# ARM_board.net
KiCad netlist of a schematic drawn in EAGLE
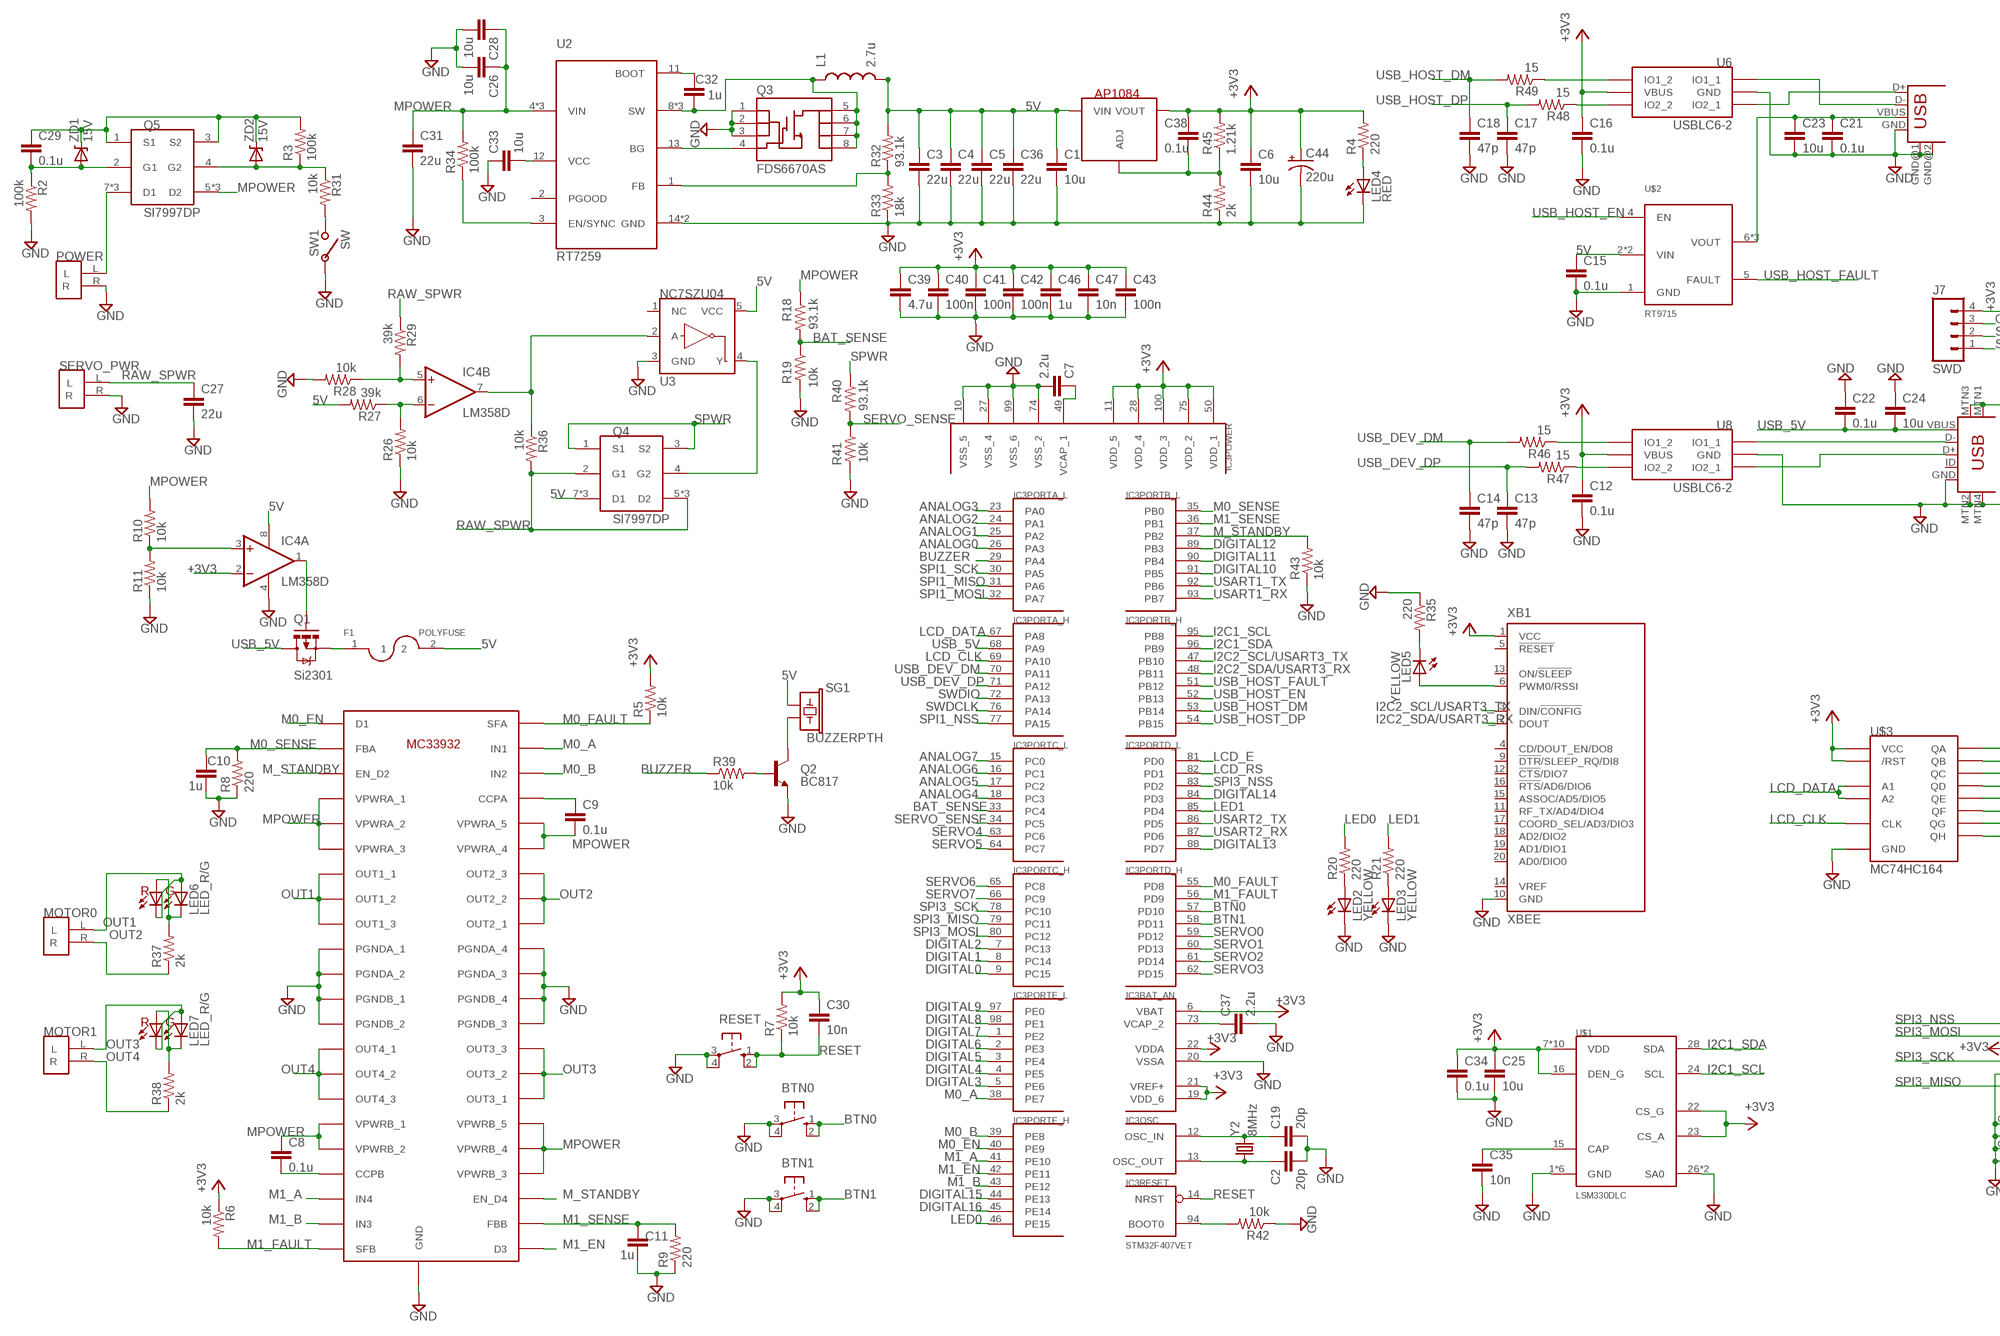
[diagram p0: schematic, sheet 1, part 1 of 2]
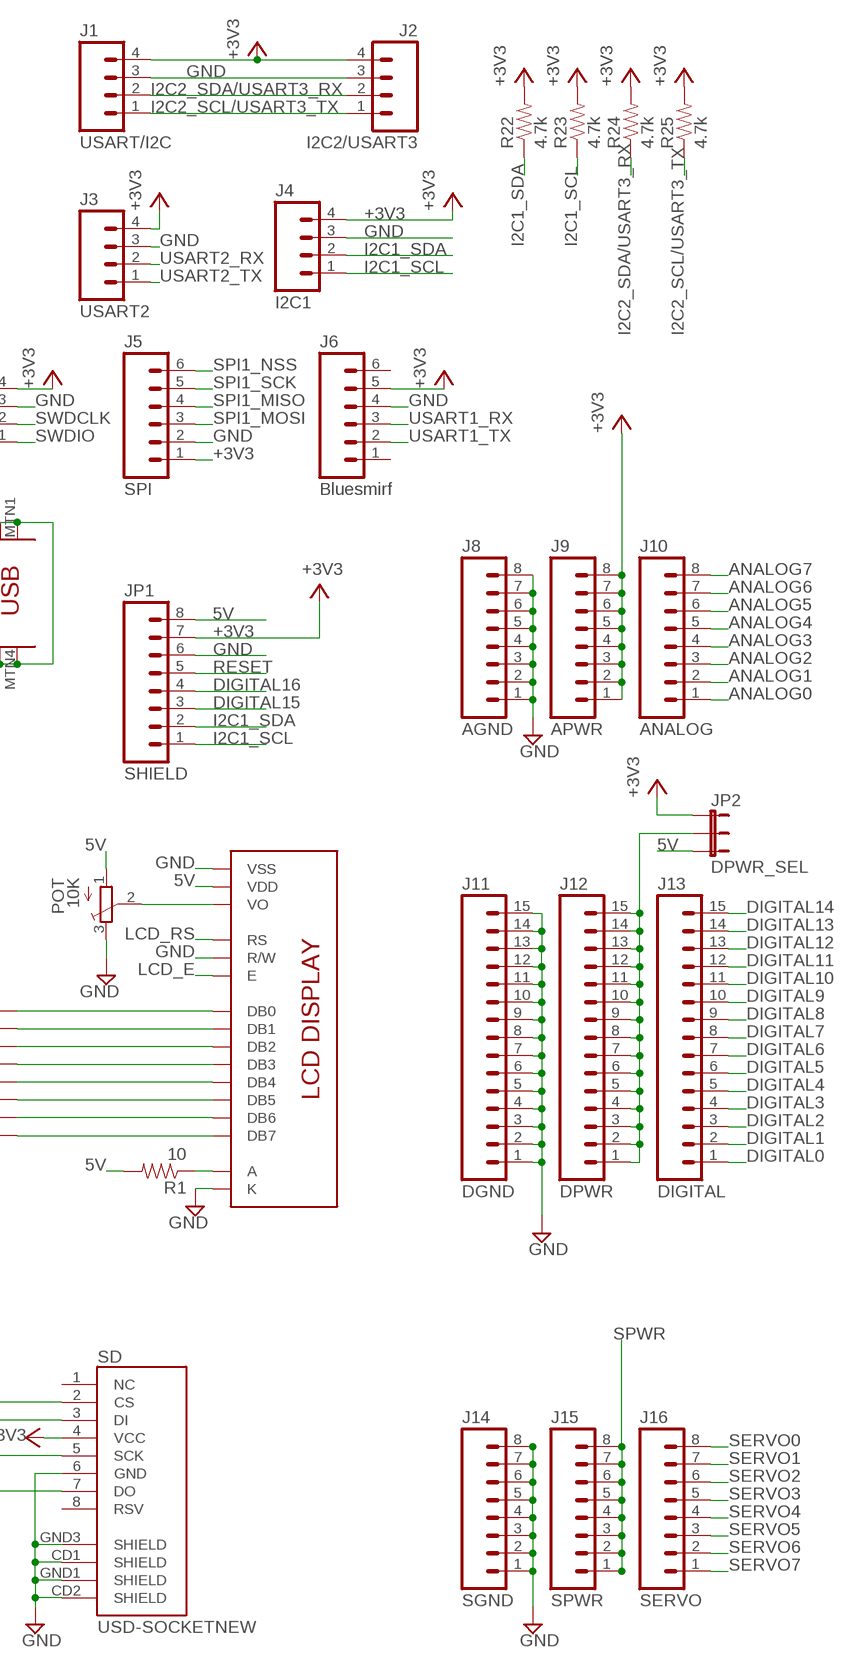
[diagram p1: schematic, sheet 1, part 2 of 2]

(export (version "E")
  (design (tool "Eeschema 10.0.6"))
  (components
    (comp (ref "AP1084")
      (value "AP1084")
      (footprint "eagle-import:DPAK")
      (libsource (lib "eagle-import") (part "AP1084"))
    )
    (comp (ref "BTN0")
      (value "10-XX")
      (footprint "eagle-import:B3F-10XX")
      (fields (field (name "MPN") "B3F-1000"))
      (libsource (lib "eagle-import") (part "10-XX"))
    )
    (comp (ref "BTN1")
      (value "10-XX")
      (footprint "eagle-import:B3F-10XX")
      (fields (field (name "MPN") "B3F-1000"))
      (libsource (lib "eagle-import") (part "10-XX"))
    )
    (comp (ref "C1")
      (value "10u")
      (footprint "eagle-import:0805")
      (libsource (lib "eagle-import") (part "CAP0805"))
    )
    (comp (ref "C2")
      (value "20p")
      (footprint "eagle-import:0603-CAP")
      (libsource (lib "eagle-import") (part "CAP0603-CAP"))
    )
    (comp (ref "C3")
      (value "22u")
      (footprint "eagle-import:0805")
      (libsource (lib "eagle-import") (part "CAP0805"))
    )
    (comp (ref "C4")
      (value "22u")
      (footprint "eagle-import:0805")
      (libsource (lib "eagle-import") (part "CAP0805"))
    )
    (comp (ref "C5")
      (value "22u")
      (footprint "eagle-import:0805")
      (libsource (lib "eagle-import") (part "CAP0805"))
    )
    (comp (ref "C6")
      (value "10u")
      (footprint "eagle-import:0805")
      (libsource (lib "eagle-import") (part "CAP0805"))
    )
    (comp (ref "C7")
      (value "2.2u")
      (footprint "eagle-import:0603-CAP")
      (libsource (lib "eagle-import") (part "CAP0603-CAP"))
    )
    (comp (ref "C8")
      (value "0.1u")
      (footprint "eagle-import:0603-CAP")
      (libsource (lib "eagle-import") (part "CAP0603-CAP"))
    )
    (comp (ref "C9")
      (value "0.1u")
      (footprint "eagle-import:0603-CAP")
      (libsource (lib "eagle-import") (part "CAP0603-CAP"))
    )
    (comp (ref "C10")
      (value "1u")
      (footprint "eagle-import:0603-CAP")
      (libsource (lib "eagle-import") (part "CAP0603-CAP"))
    )
    (comp (ref "C11")
      (value "1u")
      (footprint "eagle-import:0603-CAP")
      (libsource (lib "eagle-import") (part "CAP0603-CAP"))
    )
    (comp (ref "C12")
      (value "0.1u")
      (footprint "eagle-import:0603-CAP")
      (libsource (lib "eagle-import") (part "CAP0603-CAP"))
    )
    (comp (ref "C13")
      (value "47p")
      (footprint "eagle-import:0603-CAP")
      (libsource (lib "eagle-import") (part "CAP0603-CAP"))
    )
    (comp (ref "C14")
      (value "47p")
      (footprint "eagle-import:0603-CAP")
      (libsource (lib "eagle-import") (part "CAP0603-CAP"))
    )
    (comp (ref "C15")
      (value "0.1u")
      (footprint "eagle-import:0603-CAP")
      (libsource (lib "eagle-import") (part "CAP0603-CAP"))
    )
    (comp (ref "C16")
      (value "0.1u")
      (footprint "eagle-import:0603-CAP")
      (libsource (lib "eagle-import") (part "CAP0603-CAP"))
    )
    (comp (ref "C17")
      (value "47p")
      (footprint "eagle-import:0603-CAP")
      (libsource (lib "eagle-import") (part "CAP0603-CAP"))
    )
    (comp (ref "C18")
      (value "47p")
      (footprint "eagle-import:0603-CAP")
      (libsource (lib "eagle-import") (part "CAP0603-CAP"))
    )
    (comp (ref "C19")
      (value "20p")
      (footprint "eagle-import:0603-CAP")
      (libsource (lib "eagle-import") (part "CAP0603-CAP"))
    )
    (comp (ref "C21")
      (value "0.1u")
      (footprint "eagle-import:0603-CAP")
      (libsource (lib "eagle-import") (part "CAP0603-CAP"))
    )
    (comp (ref "C22")
      (value "0.1u")
      (footprint "eagle-import:0603-CAP")
      (libsource (lib "eagle-import") (part "CAP0603-CAP"))
    )
    (comp (ref "C23")
      (value "10u")
      (footprint "eagle-import:0805")
      (libsource (lib "eagle-import") (part "CAP0805"))
    )
    (comp (ref "C24")
      (value "10u")
      (footprint "eagle-import:0805")
      (libsource (lib "eagle-import") (part "CAP0805"))
    )
    (comp (ref "C25")
      (value "10u")
      (footprint "eagle-import:0603-CAP")
      (libsource (lib "eagle-import") (part "CAP0603-CAP"))
    )
    (comp (ref "C26")
      (value "10u")
      (footprint "eagle-import:1206")
      (libsource (lib "eagle-import") (part "CAP1206"))
    )
    (comp (ref "C27")
      (value "22u")
      (footprint "eagle-import:1206")
      (libsource (lib "eagle-import") (part "CAP1206"))
    )
    (comp (ref "C28")
      (value "10u")
      (footprint "eagle-import:1206")
      (libsource (lib "eagle-import") (part "CAP1206"))
    )
    (comp (ref "C29")
      (value "0.1u")
      (footprint "eagle-import:0603-CAP")
      (libsource (lib "eagle-import") (part "CAP0603-CAP"))
    )
    (comp (ref "C30")
      (value "10n")
      (footprint "eagle-import:0603-CAP")
      (libsource (lib "eagle-import") (part "CAP0603-CAP"))
    )
    (comp (ref "C31")
      (value "22u")
      (footprint "eagle-import:1206")
      (libsource (lib "eagle-import") (part "CAP1206"))
    )
    (comp (ref "C32")
      (value "1u")
      (footprint "eagle-import:0603-CAP")
      (libsource (lib "eagle-import") (part "CAP0603-CAP"))
    )
    (comp (ref "C33")
      (value "10u")
      (footprint "eagle-import:0805")
      (libsource (lib "eagle-import") (part "CAP0805"))
    )
    (comp (ref "C34")
      (value "0.1u")
      (footprint "eagle-import:0603-CAP")
      (libsource (lib "eagle-import") (part "CAP0603-CAP"))
    )
    (comp (ref "C35")
      (value "10n")
      (footprint "eagle-import:0603-CAP")
      (libsource (lib "eagle-import") (part "CAP0603-CAP"))
    )
    (comp (ref "C36")
      (value "22u")
      (footprint "eagle-import:0805")
      (libsource (lib "eagle-import") (part "CAP0805"))
    )
    (comp (ref "C37")
      (value "2.2u")
      (footprint "eagle-import:0603-CAP")
      (libsource (lib "eagle-import") (part "CAP0603-CAP"))
    )
    (comp (ref "C38")
      (value "0.1u")
      (footprint "eagle-import:0603-CAP")
      (libsource (lib "eagle-import") (part "CAP0603-CAP"))
    )
    (comp (ref "C39")
      (value "4.7u")
      (footprint "eagle-import:0603-CAP")
      (libsource (lib "eagle-import") (part "CAP0603-CAP"))
    )
    (comp (ref "C40")
      (value "100n")
      (footprint "eagle-import:0603-CAP")
      (libsource (lib "eagle-import") (part "CAP0603-CAP"))
    )
    (comp (ref "C41")
      (value "100n")
      (footprint "eagle-import:0603-CAP")
      (libsource (lib "eagle-import") (part "CAP0603-CAP"))
    )
    (comp (ref "C42")
      (value "100n")
      (footprint "eagle-import:0603-CAP")
      (libsource (lib "eagle-import") (part "CAP0603-CAP"))
    )
    (comp (ref "C43")
      (value "100n")
      (footprint "eagle-import:0603-CAP")
      (libsource (lib "eagle-import") (part "CAP0603-CAP"))
    )
    (comp (ref "C44")
      (value "220u")
      (footprint "eagle-import:PANASONIC_D")
      (libsource (lib "eagle-import") (part "CAP_POLD"))
    )
    (comp (ref "C46")
      (value "1u")
      (footprint "eagle-import:0603-CAP")
      (libsource (lib "eagle-import") (part "CAP0603-CAP"))
    )
    (comp (ref "C47")
      (value "10n")
      (footprint "eagle-import:0603-CAP")
      (libsource (lib "eagle-import") (part "CAP0603-CAP"))
    )
    (comp (ref "F1")
      (value "POLYFUSE")
      (footprint "eagle-import:1206")
      (libsource (lib "eagle-import") (part "POLYFUSE"))
    )
    (comp (ref "IC3")
      (value "STM32F407VET")
      (footprint "eagle-import:TQFP100")
      (libsource (lib "eagle-import") (part "STM32F407VET"))
    )
    (comp (ref "IC4")
      (value "LM358D")
      (footprint "eagle-import:SO08")
      (libsource (lib "eagle-import") (part "LM358D"))
    )
    (comp (ref "J1")
      (value "USART/I2C")
      (footprint "eagle-import:1X04")
      (libsource (lib "eagle-import") (part "M04PTH"))
    )
    (comp (ref "J2")
      (value "I2C2/USART3")
      (footprint "eagle-import:1X04")
      (libsource (lib "eagle-import") (part "M04PTH"))
    )
    (comp (ref "J3")
      (value "USART2")
      (footprint "eagle-import:1X04")
      (libsource (lib "eagle-import") (part "M04PTH"))
    )
    (comp (ref "J4")
      (value "I2C1")
      (footprint "eagle-import:1X04")
      (libsource (lib "eagle-import") (part "M04PTH"))
    )
    (comp (ref "J5")
      (value "SPI")
      (footprint "eagle-import:1X06")
      (libsource (lib "eagle-import") (part "M06SIP"))
    )
    (comp (ref "J6")
      (value "Bluesmirf")
      (footprint "eagle-import:1X06")
      (libsource (lib "eagle-import") (part "M06SIP"))
    )
    (comp (ref "J7")
      (value "SWD")
      (footprint "eagle-import:1X04")
      (libsource (lib "eagle-import") (part "M04PTH"))
    )
    (comp (ref "J8")
      (value "AGND")
      (footprint "eagle-import:1X08")
      (libsource (lib "eagle-import") (part "M081X08"))
    )
    (comp (ref "J9")
      (value "APWR")
      (footprint "eagle-import:1X08")
      (libsource (lib "eagle-import") (part "M081X08"))
    )
    (comp (ref "J10")
      (value "ANALOG")
      (footprint "eagle-import:1X08")
      (libsource (lib "eagle-import") (part "M081X08"))
    )
    (comp (ref "J11")
      (value "DGND")
      (footprint "eagle-import:1X15")
      (libsource (lib "eagle-import") (part "M15"))
    )
    (comp (ref "J12")
      (value "DPWR")
      (footprint "eagle-import:1X15")
      (libsource (lib "eagle-import") (part "M15"))
    )
    (comp (ref "J13")
      (value "DIGITAL")
      (footprint "eagle-import:1X15")
      (libsource (lib "eagle-import") (part "M15"))
    )
    (comp (ref "J14")
      (value "SGND")
      (footprint "eagle-import:1X08")
      (libsource (lib "eagle-import") (part "M081X08"))
    )
    (comp (ref "J15")
      (value "SPWR")
      (footprint "eagle-import:1X08")
      (libsource (lib "eagle-import") (part "M081X08"))
    )
    (comp (ref "J16")
      (value "SERVO")
      (footprint "eagle-import:1X08")
      (libsource (lib "eagle-import") (part "M081X08"))
    )
    (comp (ref "JP1")
      (value "SHIELD")
      (footprint "eagle-import:1X08")
      (libsource (lib "eagle-import") (part "M081X08"))
    )
    (comp (ref "JP2")
      (value "DPWR_SEL")
      (footprint "eagle-import:1X03")
      (libsource (lib "eagle-import") (part "JUMPER-3PTH"))
    )
    (comp (ref "L1")
      (value "2.7u")
      (footprint "eagle-import:INDUCTOR")
      (libsource (lib "eagle-import") (part "INDUCTOR"))
    )
    (comp (ref "LCD")
      (value "LCD_DISPLAY")
      (footprint "eagle-import:LCD")
      (libsource (lib "eagle-import") (part "LCD_DISPLAY"))
    )
    (comp (ref "LED2")
      (value "YELLOW")
      (footprint "eagle-import:CHIP-LED0603")
      (libsource (lib "eagle-import") (part "LEDCHIP-LED0603"))
    )
    (comp (ref "LED3")
      (value "YELLOW")
      (footprint "eagle-import:CHIP-LED0603")
      (libsource (lib "eagle-import") (part "LEDCHIP-LED0603"))
    )
    (comp (ref "LED4")
      (value "RED")
      (footprint "eagle-import:CHIP-LED0603")
      (libsource (lib "eagle-import") (part "LEDCHIP-LED0603"))
    )
    (comp (ref "LED5")
      (value "YELLOW")
      (footprint "eagle-import:CHIP-LED0603")
      (libsource (lib "eagle-import") (part "LEDCHIP-LED0603"))
    )
    (comp (ref "LED6")
      (value "LED_R/G")
      (footprint "eagle-import:LED-0606")
      (libsource (lib "eagle-import") (part "LED_BICOLOR"))
    )
    (comp (ref "LED7")
      (value "LED_R/G")
      (footprint "eagle-import:LED-0606")
      (libsource (lib "eagle-import") (part "LED_BICOLOR"))
    )
    (comp (ref "MOTOR0")
      (value "2POS_TERMINAL")
      (footprint "eagle-import:2POS_TERMINAL")
      (libsource (lib "eagle-import") (part "2POS_TERMINAL"))
    )
    (comp (ref "MOTOR1")
      (value "2POS_TERMINAL")
      (footprint "eagle-import:2POS_TERMINAL")
      (libsource (lib "eagle-import") (part "2POS_TERMINAL"))
    )
    (comp (ref "POT")
      (value "10K")
      (footprint "eagle-import:POT")
      (libsource (lib "eagle-import") (part "POT"))
    )
    (comp (ref "POWER")
      (value "2POS_TERMINAL")
      (footprint "eagle-import:2POS_TERMINAL")
      (libsource (lib "eagle-import") (part "2POS_TERMINAL"))
    )
    (comp (ref "Q1")
      (value "Si2301")
      (footprint "eagle-import:SOT23-3")
      (libsource (lib "eagle-import") (part "MOSFET-PCHANNELSMD"))
    )
    (comp (ref "Q2")
      (value "BC817")
      (footprint "eagle-import:SOT23-3")
      (libsource (lib "eagle-import") (part "TRANSISTOR_NPNSOT23-3"))
    )
    (comp (ref "Q3")
      (value "FDS6670AS")
      (footprint "eagle-import:SO08")
      (libsource (lib "eagle-import") (part "MOSFET-NCHANNEL-SOIC8"))
    )
    (comp (ref "Q4")
      (value "SI7997DP")
      (footprint "eagle-import:POWERPAK")
      (libsource (lib "eagle-import") (part "SI7997DP"))
    )
    (comp (ref "Q5")
      (value "SI7997DP")
      (footprint "eagle-import:POWERPAK")
      (libsource (lib "eagle-import") (part "SI7997DP"))
    )
    (comp (ref "R1")
      (value "10")
      (footprint "eagle-import:0603-RES")
      (libsource (lib "eagle-import") (part "RESISTOR0603-RES"))
    )
    (comp (ref "R2")
      (value "100k")
      (footprint "eagle-import:0603-RES")
      (libsource (lib "eagle-import") (part "RESISTOR0603-RES"))
    )
    (comp (ref "R3")
      (value "100k")
      (footprint "eagle-import:0603-RES")
      (libsource (lib "eagle-import") (part "RESISTOR0603-RES"))
    )
    (comp (ref "R4")
      (value "220")
      (footprint "eagle-import:0603-RES")
      (libsource (lib "eagle-import") (part "RESISTOR0603-RES"))
    )
    (comp (ref "R5")
      (value "10k")
      (footprint "eagle-import:0603-RES")
      (libsource (lib "eagle-import") (part "RESISTOR0603-RES"))
    )
    (comp (ref "R6")
      (value "10k")
      (footprint "eagle-import:0603-RES")
      (libsource (lib "eagle-import") (part "RESISTOR0603-RES"))
    )
    (comp (ref "R7")
      (value "10k")
      (footprint "eagle-import:0603-RES")
      (libsource (lib "eagle-import") (part "RESISTOR0603-RES"))
    )
    (comp (ref "R8")
      (value "220")
      (footprint "eagle-import:0603-RES")
      (libsource (lib "eagle-import") (part "RESISTOR0603-RES"))
    )
    (comp (ref "R9")
      (value "220")
      (footprint "eagle-import:0603-RES")
      (libsource (lib "eagle-import") (part "RESISTOR0603-RES"))
    )
    (comp (ref "R10")
      (value "10k")
      (footprint "eagle-import:0603-RES")
      (libsource (lib "eagle-import") (part "RESISTOR0603-RES"))
    )
    (comp (ref "R11")
      (value "10k")
      (footprint "eagle-import:0603-RES")
      (libsource (lib "eagle-import") (part "RESISTOR0603-RES"))
    )
    (comp (ref "R18")
      (value "93.1k")
      (footprint "eagle-import:0603-RES")
      (libsource (lib "eagle-import") (part "RESISTOR0603-RES"))
    )
    (comp (ref "R19")
      (value "10k")
      (footprint "eagle-import:0603-RES")
      (libsource (lib "eagle-import") (part "RESISTOR0603-RES"))
    )
    (comp (ref "R20")
      (value "220")
      (footprint "eagle-import:0603-RES")
      (libsource (lib "eagle-import") (part "RESISTOR0603-RES"))
    )
    (comp (ref "R21")
      (value "220")
      (footprint "eagle-import:0603-RES")
      (libsource (lib "eagle-import") (part "RESISTOR0603-RES"))
    )
    (comp (ref "R22")
      (value "4.7k")
      (footprint "eagle-import:0603-RES")
      (libsource (lib "eagle-import") (part "RESISTOR0603-RES"))
    )
    (comp (ref "R23")
      (value "4.7k")
      (footprint "eagle-import:0603-RES")
      (libsource (lib "eagle-import") (part "RESISTOR0603-RES"))
    )
    (comp (ref "R24")
      (value "4.7k")
      (footprint "eagle-import:0603-RES")
      (libsource (lib "eagle-import") (part "RESISTOR0603-RES"))
    )
    (comp (ref "R25")
      (value "4.7k")
      (footprint "eagle-import:0603-RES")
      (libsource (lib "eagle-import") (part "RESISTOR0603-RES"))
    )
    (comp (ref "R26")
      (value "10k")
      (footprint "eagle-import:0603-RES")
      (libsource (lib "eagle-import") (part "RESISTOR0603-RES"))
    )
    (comp (ref "R27")
      (value "39k")
      (footprint "eagle-import:0603-RES")
      (libsource (lib "eagle-import") (part "RESISTOR0603-RES"))
    )
    (comp (ref "R28")
      (value "10k")
      (footprint "eagle-import:0603-RES")
      (libsource (lib "eagle-import") (part "RESISTOR0603-RES"))
    )
    (comp (ref "R29")
      (value "39k")
      (footprint "eagle-import:0603-RES")
      (libsource (lib "eagle-import") (part "RESISTOR0603-RES"))
    )
    (comp (ref "R31")
      (value "10k")
      (footprint "eagle-import:0603-RES")
      (libsource (lib "eagle-import") (part "RESISTOR0603-RES"))
    )
    (comp (ref "R32")
      (value "93.1k")
      (footprint "eagle-import:0603-RES")
      (libsource (lib "eagle-import") (part "RESISTOR0603-RES"))
    )
    (comp (ref "R33")
      (value "18k")
      (footprint "eagle-import:0603-RES")
      (libsource (lib "eagle-import") (part "RESISTOR0603-RES"))
    )
    (comp (ref "R34")
      (value "100k")
      (footprint "eagle-import:0603-RES")
      (libsource (lib "eagle-import") (part "RESISTOR0603-RES"))
    )
    (comp (ref "R35")
      (value "220")
      (footprint "eagle-import:0603-RES")
      (libsource (lib "eagle-import") (part "RESISTOR0603-RES"))
    )
    (comp (ref "R36")
      (value "10k")
      (footprint "eagle-import:0603-RES")
      (libsource (lib "eagle-import") (part "RESISTOR0603-RES"))
    )
    (comp (ref "R37")
      (value "2k")
      (footprint "eagle-import:0603-RES")
      (libsource (lib "eagle-import") (part "RESISTOR0603-RES"))
    )
    (comp (ref "R38")
      (value "2k")
      (footprint "eagle-import:0603-RES")
      (libsource (lib "eagle-import") (part "RESISTOR0603-RES"))
    )
    (comp (ref "R39")
      (value "10k")
      (footprint "eagle-import:0603-RES")
      (libsource (lib "eagle-import") (part "RESISTOR0603-RES"))
    )
    (comp (ref "R40")
      (value "93.1k")
      (footprint "eagle-import:0603-RES")
      (libsource (lib "eagle-import") (part "RESISTOR0603-RES"))
    )
    (comp (ref "R41")
      (value "10k")
      (footprint "eagle-import:0603-RES")
      (libsource (lib "eagle-import") (part "RESISTOR0603-RES"))
    )
    (comp (ref "R42")
      (value "10k")
      (footprint "eagle-import:0603-RES")
      (libsource (lib "eagle-import") (part "RESISTOR0603-RES"))
    )
    (comp (ref "R43")
      (value "10k")
      (footprint "eagle-import:0603-RES")
      (libsource (lib "eagle-import") (part "RESISTOR0603-RES"))
    )
    (comp (ref "R44")
      (value "2k")
      (footprint "eagle-import:0603-RES")
      (libsource (lib "eagle-import") (part "RESISTOR0603-RES"))
    )
    (comp (ref "R45")
      (value "1.21k")
      (footprint "eagle-import:0603-RES")
      (libsource (lib "eagle-import") (part "RESISTOR0603-RES"))
    )
    (comp (ref "R46")
      (value "15")
      (footprint "eagle-import:0603-RES")
      (libsource (lib "eagle-import") (part "RESISTOR0603-RES"))
    )
    (comp (ref "R47")
      (value "15")
      (footprint "eagle-import:0603-RES")
      (libsource (lib "eagle-import") (part "RESISTOR0603-RES"))
    )
    (comp (ref "R48")
      (value "15")
      (footprint "eagle-import:0603-RES")
      (libsource (lib "eagle-import") (part "RESISTOR0603-RES"))
    )
    (comp (ref "R49")
      (value "15")
      (footprint "eagle-import:0603-RES")
      (libsource (lib "eagle-import") (part "RESISTOR0603-RES"))
    )
    (comp (ref "RESET")
      (value "10-XX")
      (footprint "eagle-import:B3F-10XX")
      (fields (field (name "MPN") "B3F-1000"))
      (libsource (lib "eagle-import") (part "10-XX"))
    )
    (comp (ref "SD")
      (value "USD-SOCKETNEW")
      (footprint "eagle-import:MICRO-SD-SOCKET-PP")
      (libsource (lib "eagle-import") (part "USD-SOCKETNEW"))
    )
    (comp (ref "SERVO_PWR")
      (value "2POS_TERMINAL")
      (footprint "eagle-import:2POS_TERMINAL")
      (libsource (lib "eagle-import") (part "2POS_TERMINAL"))
    )
    (comp (ref "SG1")
      (value "BUZZERPTH")
      (footprint "eagle-import:BUZZER-12MM")
      (libsource (lib "eagle-import") (part "BUZZERPTH"))
    )
    (comp (ref "SW1") (value "SW") (footprint "eagle-import:SW") (libsource (lib "eagle-import") (part "SW")))
    (comp (ref "U$1")
      (value "LSM330DLC")
      (footprint "eagle-import:LGA-28")
      (libsource (lib "eagle-import") (part "LSM330DLC"))
    )
    (comp (ref "U$2")
      (value "RT9715")
      (footprint "eagle-import:8-SOIC")
      (libsource (lib "eagle-import") (part "RT9715"))
    )
    (comp (ref "U$3")
      (value "MC74HC164")
      (footprint "eagle-import:TSSOP-14")
      (libsource (lib "eagle-import") (part "MC74HC164"))
    )
    (comp (ref "U1")
      (value "MC33932")
      (footprint "eagle-import:HSOP44")
      (libsource (lib "eagle-import") (part "MC33932"))
    )
    (comp (ref "U2")
      (value "RT7259")
      (footprint "eagle-import:WDFN-14L")
      (libsource (lib "eagle-import") (part "SWITCHING_REG"))
    )
    (comp (ref "U3")
      (value "NC7SZU04")
      (footprint "eagle-import:SC70")
      (libsource (lib "eagle-import") (part "INVERTER{dblquote}{dblquote}"))
    )
    (comp (ref "U6")
      (value "USBLC6-2")
      (footprint "eagle-import:SOT23-6L")
      (libsource (lib "eagle-import") (part "USBLC6-2"))
    )
    (comp (ref "U8")
      (value "USBLC6-2")
      (footprint "eagle-import:SOT23-6L")
      (libsource (lib "eagle-import") (part "USBLC6-2"))
    )
    (comp (ref "USB1")
      (value "USB-A-S")
      (footprint "eagle-import:USB-A-S")
      (libsource (lib "eagle-import") (part "USB-A-S"))
    )
    (comp (ref "USB2")
      (value "USB-MINIB-5PIN")
      (footprint "eagle-import:USB-MINIB")
      (libsource (lib "eagle-import") (part "USB-MINIB-5PIN"))
    )
    (comp (ref "XB1")
      (value "XBEE")
      (footprint "eagle-import:XBEE")
      (fields
        (field (name "MPN") "XBP24-Z7UIT-004")
        (field (name "MPN_1") "XBP24-Z7UIT-004")
        (field (name "OC_FARNELL") "1751799")
        (field (name "OC_NEWARK") "34R5507")
      )
      (libsource (lib "eagle-import") (part "XBEE"))
    )
    (comp (ref "Y2")
      (value "8MHz")
      (footprint "eagle-import:HC49UP")
      (libsource (lib "eagle-import") (part "CRYSTALSMD"))
    )
    (comp (ref "ZD1")
      (value "15V")
      (footprint "eagle-import:0603")
      (libsource (lib "eagle-import") (part "ZENER"))
    )
    (comp (ref "ZD2")
      (value "15V")
      (footprint "eagle-import:0603")
      (libsource (lib "eagle-import") (part "ZENER"))
    )
  )
  (nets
    (net (code "1") (name "+3V3") (class "Default")
      (node (ref "AP1084") (pin "TAB") (pinfunction "VOUT_TAB") (pintype "bidirectional"))
      (node (ref "C12") (pin "1") (pinfunction "1_1") (pintype "passive"))
      (node (ref "C16") (pin "1") (pinfunction "1_1") (pintype "passive"))
      (node (ref "C25") (pin "1") (pinfunction "1_1") (pintype "passive"))
      (node (ref "C30") (pin "1") (pinfunction "1_1") (pintype "passive"))
      (node (ref "C34") (pin "1") (pinfunction "1_1") (pintype "passive"))
      (node (ref "C38") (pin "1") (pinfunction "1_1") (pintype "passive"))
      (node (ref "C39") (pin "1") (pinfunction "1_1") (pintype "passive"))
      (node (ref "C40") (pin "1") (pinfunction "1_1") (pintype "passive"))
      (node (ref "C41") (pin "1") (pinfunction "1_1") (pintype "passive"))
      (node (ref "C42") (pin "1") (pinfunction "1_1") (pintype "passive"))
      (node (ref "C43") (pin "1") (pinfunction "1_1") (pintype "passive"))
      (node (ref "C44") (pin "+") (pinfunction "+_+") (pintype "passive"))
      (node (ref "C46") (pin "1") (pinfunction "1_1") (pintype "passive"))
      (node (ref "C47") (pin "1") (pinfunction "1_1") (pintype "passive"))
      (node (ref "C6") (pin "1") (pinfunction "1_1") (pintype "passive"))
      (node (ref "IC3") (pin "100") (pinfunction "VDD_3_100") (pintype "power_in"))
      (node (ref "IC3") (pin "11") (pinfunction "VDD_5_11") (pintype "power_in"))
      (node (ref "IC3") (pin "19") (pinfunction "VDD_6_19") (pintype "input"))
      (node (ref "IC3") (pin "21") (pinfunction "VREF+_21") (pintype "input"))
      (node (ref "IC3") (pin "22") (pinfunction "VDDA_22") (pintype "power_in"))
      (node (ref "IC3") (pin "28") (pinfunction "VDD_4_28") (pintype "power_in"))
      (node (ref "IC3") (pin "50") (pinfunction "VDD_1_50") (pintype "power_in"))
      (node (ref "IC3") (pin "6") (pinfunction "VBAT_6") (pintype "power_in"))
      (node (ref "IC3") (pin "75") (pinfunction "VDD_2_75") (pintype "power_in"))
      (node (ref "IC4") (pin "2") (pinfunction "-IN_2") (pintype "input"))
      (node (ref "J1") (pin "4") (pinfunction "4_4") (pintype "passive"))
      (node (ref "J2") (pin "4") (pinfunction "4_4") (pintype "passive"))
      (node (ref "J3") (pin "4") (pinfunction "4_4") (pintype "passive"))
      (node (ref "J4") (pin "4") (pinfunction "4_4") (pintype "passive"))
      (node (ref "J5") (pin "1") (pinfunction "1_1") (pintype "passive"))
      (node (ref "J6") (pin "5") (pinfunction "5_5") (pintype "passive"))
      (node (ref "J7") (pin "4") (pinfunction "4_4") (pintype "passive"))
      (node (ref "J9") (pin "1") (pinfunction "1_1") (pintype "passive"))
      (node (ref "J9") (pin "2") (pinfunction "2_2") (pintype "passive"))
      (node (ref "J9") (pin "3") (pinfunction "3_3") (pintype "passive"))
      (node (ref "J9") (pin "4") (pinfunction "4_4") (pintype "passive"))
      (node (ref "J9") (pin "5") (pinfunction "5_5") (pintype "passive"))
      (node (ref "J9") (pin "6") (pinfunction "6_6") (pintype "passive"))
      (node (ref "J9") (pin "7") (pinfunction "7_7") (pintype "passive"))
      (node (ref "J9") (pin "8") (pinfunction "8_8") (pintype "passive"))
      (node (ref "JP1") (pin "7") (pinfunction "7_7") (pintype "passive"))
      (node (ref "JP2") (pin "1") (pinfunction "1_1") (pintype "passive"))
      (node (ref "R22") (pin "2") (pinfunction "2_2") (pintype "passive"))
      (node (ref "R23") (pin "2") (pinfunction "2_2") (pintype "passive"))
      (node (ref "R24") (pin "2") (pinfunction "2_2") (pintype "passive"))
      (node (ref "R25") (pin "2") (pinfunction "2_2") (pintype "passive"))
      (node (ref "R4") (pin "2") (pinfunction "2_2") (pintype "passive"))
      (node (ref "R45") (pin "2") (pinfunction "2_2") (pintype "passive"))
      (node (ref "R5") (pin "2") (pinfunction "2_2") (pintype "passive"))
      (node (ref "R6") (pin "1") (pinfunction "1_1") (pintype "passive"))
      (node (ref "R7") (pin "2") (pinfunction "2_2") (pintype "passive"))
      (node (ref "SD") (pin "4") (pinfunction "VCC_4") (pintype "bidirectional"))
      (node (ref "U$1") (pin "10") (pinfunction "VDD_10") (pintype "bidirectional"))
      (node (ref "U$1") (pin "11") (pinfunction "VDD_11") (pintype "bidirectional"))
      (node (ref "U$1") (pin "12") (pinfunction "VDD_12") (pintype "bidirectional"))
      (node (ref "U$1") (pin "13") (pinfunction "VDD_13") (pintype "bidirectional"))
      (node (ref "U$1") (pin "14") (pinfunction "VDD_14") (pintype "bidirectional"))
      (node (ref "U$1") (pin "16") (pinfunction "DEN_G_16") (pintype "bidirectional"))
      (node (ref "U$1") (pin "21") (pinfunction "VDD_21") (pintype "bidirectional"))
      (node (ref "U$1") (pin "22") (pinfunction "CS_G_22") (pintype "bidirectional"))
      (node (ref "U$1") (pin "23") (pinfunction "CS_A_23") (pintype "bidirectional"))
      (node (ref "U$1") (pin "25") (pinfunction "VDD_25") (pintype "bidirectional"))
      (node (ref "U$1") (pin "7") (pinfunction "VDD_7") (pintype "bidirectional"))
      (node (ref "U$1") (pin "8") (pinfunction "VDD_8") (pintype "bidirectional"))
      (node (ref "U$1") (pin "9") (pinfunction "VDD_9") (pintype "bidirectional"))
      (node (ref "U$3") (pin "14") (pinfunction "VCC_14") (pintype "bidirectional"))
      (node (ref "U$3") (pin "9") (pinfunction "/RST_9") (pintype "bidirectional"))
      (node (ref "U6") (pin "P$5") (pinfunction "VBUS_P$5") (pintype "bidirectional"))
      (node (ref "U8") (pin "P$5") (pinfunction "VBUS_P$5") (pintype "bidirectional"))
      (node (ref "XB1") (pin "1") (pinfunction "VCC_1") (pintype "power_in"))
    )
    (net (code "2") (name "/5V") (class "Default")
      (node (ref "AP1084") (pin "3") (pinfunction "VIN_3") (pintype "bidirectional"))
      (node (ref "C1") (pin "1") (pinfunction "1_1") (pintype "passive"))
      (node (ref "C15") (pin "1") (pinfunction "1_1") (pintype "passive"))
      (node (ref "C3") (pin "1") (pinfunction "1_1") (pintype "passive"))
      (node (ref "C36") (pin "1") (pinfunction "1_1") (pintype "passive"))
      (node (ref "C4") (pin "1") (pinfunction "1_1") (pintype "passive"))
      (node (ref "C5") (pin "1") (pinfunction "1_1") (pintype "passive"))
      (node (ref "F1") (pin "2") (pinfunction "2_2") (pintype "bidirectional"))
      (node (ref "IC4") (pin "8") (pinfunction "V+_8") (pintype "power_in"))
      (node (ref "JP1") (pin "8") (pinfunction "8_8") (pintype "passive"))
      (node (ref "JP2") (pin "3") (pinfunction "3_3") (pintype "passive"))
      (node (ref "L1") (pin "P$2") (pinfunction "2_P$2") (pintype "passive"))
      (node (ref "LCD") (pin "VDD") (pinfunction "VDD_VDD") (pintype "bidirectional"))
      (node (ref "POT") (pin "1") (pinfunction "A_1") (pintype "passive"))
      (node (ref "Q4") (pin "7") (pinfunction "D1_7") (pintype "bidirectional"))
      (node (ref "Q4") (pin "8") (pinfunction "D1_8") (pintype "bidirectional"))
      (node (ref "Q4") (pin "9") (pinfunction "D1_9") (pintype "bidirectional"))
      (node (ref "R1") (pin "2") (pinfunction "2_2") (pintype "passive"))
      (node (ref "R27") (pin "2") (pinfunction "2_2") (pintype "passive"))
      (node (ref "R32") (pin "2") (pinfunction "2_2") (pintype "passive"))
      (node (ref "SG1") (pin "+") (pinfunction "1_+") (pintype "passive"))
      (node (ref "U$2") (pin "2") (pinfunction "VIN_2") (pintype "bidirectional"))
      (node (ref "U$2") (pin "3") (pinfunction "VIN_3") (pintype "bidirectional"))
      (node (ref "U3") (pin "5") (pinfunction "VCC_5") (pintype "bidirectional"))
    )
    (net (code "3") (name "/ANALOG0") (class "Default")
      (node (ref "IC3") (pin "26") (pinfunction "PA3_26") (pintype "bidirectional"))
      (node (ref "J10") (pin "1") (pinfunction "1_1") (pintype "passive"))
    )
    (net (code "4") (name "/ANALOG1") (class "Default")
      (node (ref "IC3") (pin "25") (pinfunction "PA2_25") (pintype "bidirectional"))
      (node (ref "J10") (pin "2") (pinfunction "2_2") (pintype "passive"))
    )
    (net (code "5") (name "/ANALOG2") (class "Default")
      (node (ref "IC3") (pin "24") (pinfunction "PA1_24") (pintype "bidirectional"))
      (node (ref "J10") (pin "3") (pinfunction "3_3") (pintype "passive"))
    )
    (net (code "6") (name "/ANALOG3") (class "Default")
      (node (ref "IC3") (pin "23") (pinfunction "PA0_23") (pintype "bidirectional"))
      (node (ref "J10") (pin "4") (pinfunction "4_4") (pintype "passive"))
    )
    (net (code "7") (name "/ANALOG4") (class "Default")
      (node (ref "IC3") (pin "18") (pinfunction "PC3_18") (pintype "bidirectional"))
      (node (ref "J10") (pin "5") (pinfunction "5_5") (pintype "passive"))
    )
    (net (code "8") (name "/ANALOG5") (class "Default")
      (node (ref "IC3") (pin "17") (pinfunction "PC2_17") (pintype "bidirectional"))
      (node (ref "J10") (pin "6") (pinfunction "6_6") (pintype "passive"))
    )
    (net (code "9") (name "/ANALOG6") (class "Default")
      (node (ref "IC3") (pin "16") (pinfunction "PC1_16") (pintype "bidirectional"))
      (node (ref "J10") (pin "7") (pinfunction "7_7") (pintype "passive"))
    )
    (net (code "10") (name "/ANALOG7") (class "Default")
      (node (ref "IC3") (pin "15") (pinfunction "PC0_15") (pintype "bidirectional"))
      (node (ref "J10") (pin "8") (pinfunction "8_8") (pintype "passive"))
    )
    (net (code "11") (name "/BAT_SENSE") (class "Default")
      (node (ref "IC3") (pin "33") (pinfunction "PC4_33") (pintype "bidirectional"))
      (node (ref "R18") (pin "2") (pinfunction "2_2") (pintype "passive"))
      (node (ref "R19") (pin "1") (pinfunction "1_1") (pintype "passive"))
    )
    (net (code "12") (name "/BTN0") (class "Default")
      (node (ref "BTN0") (pin "1") (pinfunction "S_1") (pintype "passive"))
      (node (ref "BTN0") (pin "2") (pinfunction "S1_2") (pintype "passive"))
      (node (ref "IC3") (pin "57") (pinfunction "PD10_57") (pintype "bidirectional"))
    )
    (net (code "13") (name "/BTN1") (class "Default")
      (node (ref "BTN1") (pin "1") (pinfunction "S_1") (pintype "passive"))
      (node (ref "BTN1") (pin "2") (pinfunction "S1_2") (pintype "passive"))
      (node (ref "IC3") (pin "58") (pinfunction "PD11_58") (pintype "bidirectional"))
    )
    (net (code "14") (name "/BUZZER") (class "Default")
      (node (ref "IC3") (pin "29") (pinfunction "PA4_29") (pintype "bidirectional"))
      (node (ref "R39") (pin "1") (pinfunction "1_1") (pintype "passive"))
    )
    (net (code "15") (name "/DIGITAL0") (class "Default")
      (node (ref "IC3") (pin "9") (pinfunction "PC15_9") (pintype "bidirectional"))
      (node (ref "J13") (pin "1") (pinfunction "1_1") (pintype "passive"))
    )
    (net (code "16") (name "/DIGITAL1") (class "Default")
      (node (ref "IC3") (pin "8") (pinfunction "PC14_8") (pintype "bidirectional"))
      (node (ref "J13") (pin "2") (pinfunction "2_2") (pintype "passive"))
    )
    (net (code "17") (name "/DIGITAL2") (class "Default")
      (node (ref "IC3") (pin "7") (pinfunction "PC13_7") (pintype "bidirectional"))
      (node (ref "J13") (pin "3") (pinfunction "3_3") (pintype "passive"))
    )
    (net (code "18") (name "/DIGITAL3") (class "Default")
      (node (ref "IC3") (pin "5") (pinfunction "PE6_5") (pintype "bidirectional"))
      (node (ref "J13") (pin "4") (pinfunction "4_4") (pintype "passive"))
    )
    (net (code "19") (name "/DIGITAL4") (class "Default")
      (node (ref "IC3") (pin "4") (pinfunction "PE5_4") (pintype "bidirectional"))
      (node (ref "J13") (pin "5") (pinfunction "5_5") (pintype "passive"))
    )
    (net (code "20") (name "/DIGITAL5") (class "Default")
      (node (ref "IC3") (pin "3") (pinfunction "PE4_3") (pintype "bidirectional"))
      (node (ref "J13") (pin "6") (pinfunction "6_6") (pintype "passive"))
    )
    (net (code "21") (name "/DIGITAL6") (class "Default")
      (node (ref "IC3") (pin "2") (pinfunction "PE3_2") (pintype "bidirectional"))
      (node (ref "J13") (pin "7") (pinfunction "7_7") (pintype "passive"))
    )
    (net (code "22") (name "/DIGITAL7") (class "Default")
      (node (ref "IC3") (pin "1") (pinfunction "PE2_1") (pintype "bidirectional"))
      (node (ref "J13") (pin "8") (pinfunction "8_8") (pintype "passive"))
    )
    (net (code "23") (name "/DIGITAL8") (class "Default")
      (node (ref "IC3") (pin "98") (pinfunction "PE1_98") (pintype "bidirectional"))
      (node (ref "J13") (pin "9") (pinfunction "9_9") (pintype "passive"))
    )
    (net (code "24") (name "/DIGITAL9") (class "Default")
      (node (ref "IC3") (pin "97") (pinfunction "PE0_97") (pintype "bidirectional"))
      (node (ref "J13") (pin "10") (pinfunction "10_10") (pintype "passive"))
    )
    (net (code "25") (name "/DIGITAL10") (class "Default")
      (node (ref "IC3") (pin "91") (pinfunction "PB5_91") (pintype "bidirectional"))
      (node (ref "J13") (pin "11") (pinfunction "11_11") (pintype "passive"))
    )
    (net (code "26") (name "/DIGITAL11") (class "Default")
      (node (ref "IC3") (pin "90") (pinfunction "PB4_90") (pintype "bidirectional"))
      (node (ref "J13") (pin "12") (pinfunction "12_12") (pintype "passive"))
    )
    (net (code "27") (name "/DIGITAL12") (class "Default")
      (node (ref "IC3") (pin "89") (pinfunction "PB3_89") (pintype "bidirectional"))
      (node (ref "J13") (pin "13") (pinfunction "13_13") (pintype "passive"))
    )
    (net (code "28") (name "/DIGITAL13") (class "Default")
      (node (ref "IC3") (pin "88") (pinfunction "PD7_88") (pintype "bidirectional"))
      (node (ref "J13") (pin "14") (pinfunction "14_14") (pintype "passive"))
    )
    (net (code "29") (name "/DIGITAL14") (class "Default")
      (node (ref "IC3") (pin "84") (pinfunction "PD3_84") (pintype "bidirectional"))
      (node (ref "J13") (pin "15") (pinfunction "15_15") (pintype "passive"))
    )
    (net (code "30") (name "/DIGITAL15") (class "Default")
      (node (ref "IC3") (pin "44") (pinfunction "PE13_44") (pintype "bidirectional"))
      (node (ref "JP1") (pin "3") (pinfunction "3_3") (pintype "passive"))
    )
    (net (code "31") (name "/DIGITAL16") (class "Default")
      (node (ref "IC3") (pin "45") (pinfunction "PE14_45") (pintype "bidirectional"))
      (node (ref "JP1") (pin "4") (pinfunction "4_4") (pintype "passive"))
    )
    (net (code "32") (name "/I2C1_SCL") (class "Default")
      (node (ref "IC3") (pin "95") (pinfunction "PB8_95") (pintype "bidirectional"))
      (node (ref "J4") (pin "1") (pinfunction "1_1") (pintype "passive"))
      (node (ref "JP1") (pin "1") (pinfunction "1_1") (pintype "passive"))
      (node (ref "R23") (pin "1") (pinfunction "1_1") (pintype "passive"))
      (node (ref "U$1") (pin "24") (pinfunction "SCL_24") (pintype "bidirectional"))
    )
    (net (code "33") (name "/I2C1_SDA") (class "Default")
      (node (ref "IC3") (pin "96") (pinfunction "PB9_96") (pintype "bidirectional"))
      (node (ref "J4") (pin "2") (pinfunction "2_2") (pintype "passive"))
      (node (ref "JP1") (pin "2") (pinfunction "2_2") (pintype "passive"))
      (node (ref "R22") (pin "1") (pinfunction "1_1") (pintype "passive"))
      (node (ref "U$1") (pin "28") (pinfunction "SDA_28") (pintype "bidirectional"))
    )
    (net (code "34") (name "/I2C2_SCL{slash}USART3_TX") (class "Default")
      (node (ref "IC3") (pin "47") (pinfunction "PB10_47") (pintype "bidirectional"))
      (node (ref "J1") (pin "1") (pinfunction "1_1") (pintype "passive"))
      (node (ref "J2") (pin "1") (pinfunction "1_1") (pintype "passive"))
      (node (ref "R25") (pin "1") (pinfunction "1_1") (pintype "passive"))
      (node (ref "XB1") (pin "3") (pinfunction "DIN/~{CONFIG}_3") (pintype "input"))
    )
    (net (code "35") (name "/I2C2_SDA{slash}USART3_RX") (class "Default")
      (node (ref "IC3") (pin "48") (pinfunction "PB11_48") (pintype "bidirectional"))
      (node (ref "J1") (pin "2") (pinfunction "2_2") (pintype "passive"))
      (node (ref "J2") (pin "2") (pinfunction "2_2") (pintype "passive"))
      (node (ref "R24") (pin "1") (pinfunction "1_1") (pintype "passive"))
      (node (ref "XB1") (pin "2") (pinfunction "DOUT_2") (pintype "output"))
    )
    (net (code "36") (name "/LCD_CLK") (class "Default")
      (node (ref "IC3") (pin "69") (pinfunction "PA10_69") (pintype "bidirectional"))
      (node (ref "U$3") (pin "8") (pinfunction "CLK_8") (pintype "bidirectional"))
    )
    (net (code "37") (name "/LCD_DATA") (class "Default")
      (node (ref "IC3") (pin "67") (pinfunction "PA8_67") (pintype "bidirectional"))
      (node (ref "U$3") (pin "1") (pinfunction "A1_1") (pintype "bidirectional"))
      (node (ref "U$3") (pin "2") (pinfunction "A2_2") (pintype "bidirectional"))
    )
    (net (code "38") (name "/LCD_E") (class "Default")
      (node (ref "IC3") (pin "81") (pinfunction "PD0_81") (pintype "bidirectional"))
      (node (ref "LCD") (pin "E") (pinfunction "E_E") (pintype "bidirectional"))
    )
    (net (code "39") (name "/LCD_RS") (class "Default")
      (node (ref "IC3") (pin "82") (pinfunction "PD1_82") (pintype "bidirectional"))
      (node (ref "LCD") (pin "RS") (pinfunction "RS_RS") (pintype "bidirectional"))
    )
    (net (code "40") (name "/LED0") (class "Default")
      (node (ref "IC3") (pin "46") (pinfunction "PE15_46") (pintype "bidirectional"))
      (node (ref "R20") (pin "2") (pinfunction "2_2") (pintype "passive"))
    )
    (net (code "41") (name "/LED1") (class "Default")
      (node (ref "IC3") (pin "85") (pinfunction "PD4_85") (pintype "bidirectional"))
      (node (ref "R21") (pin "2") (pinfunction "2_2") (pintype "passive"))
    )
    (net (code "42") (name "/M0_A") (class "Default")
      (node (ref "IC3") (pin "38") (pinfunction "PE7_38") (pintype "bidirectional"))
      (node (ref "U1") (pin "P$43") (pinfunction "IN1_P$43") (pintype "bidirectional"))
    )
    (net (code "43") (name "/M0_B") (class "Default")
      (node (ref "IC3") (pin "39") (pinfunction "PE8_39") (pintype "bidirectional"))
      (node (ref "U1") (pin "P$42") (pinfunction "IN2_P$42") (pintype "bidirectional"))
    )
    (net (code "44") (name "/M0_EN") (class "Default")
      (node (ref "IC3") (pin "40") (pinfunction "PE9_40") (pintype "bidirectional"))
      (node (ref "U1") (pin "P$1") (pinfunction "D1_P$1") (pintype "bidirectional"))
    )
    (net (code "45") (name "/M0_FAULT") (class "Default")
      (node (ref "IC3") (pin "55") (pinfunction "PD8_55") (pintype "bidirectional"))
      (node (ref "R5") (pin "1") (pinfunction "1_1") (pintype "passive"))
      (node (ref "U1") (pin "P$44") (pinfunction "SFA_P$44") (pintype "bidirectional"))
    )
    (net (code "46") (name "/M0_SENSE") (class "Default")
      (node (ref "C10") (pin "1") (pinfunction "1_1") (pintype "passive"))
      (node (ref "IC3") (pin "35") (pinfunction "PB0_35") (pintype "bidirectional"))
      (node (ref "R8") (pin "2") (pinfunction "2_2") (pintype "passive"))
      (node (ref "U1") (pin "P$2") (pinfunction "FBA_P$2") (pintype "bidirectional"))
    )
    (net (code "47") (name "/M1_A") (class "Default")
      (node (ref "IC3") (pin "41") (pinfunction "PE10_41") (pintype "bidirectional"))
      (node (ref "U1") (pin "P$20") (pinfunction "IN4_P$20") (pintype "bidirectional"))
    )
    (net (code "48") (name "/M1_B") (class "Default")
      (node (ref "IC3") (pin "43") (pinfunction "PE12_43") (pintype "bidirectional"))
      (node (ref "U1") (pin "P$21") (pinfunction "IN3_P$21") (pintype "bidirectional"))
    )
    (net (code "49") (name "/M1_EN") (class "Default")
      (node (ref "IC3") (pin "42") (pinfunction "PE11_42") (pintype "bidirectional"))
      (node (ref "U1") (pin "P$23") (pinfunction "D3_P$23") (pintype "bidirectional"))
    )
    (net (code "50") (name "/M1_FAULT") (class "Default")
      (node (ref "IC3") (pin "56") (pinfunction "PD9_56") (pintype "bidirectional"))
      (node (ref "R6") (pin "2") (pinfunction "2_2") (pintype "passive"))
      (node (ref "U1") (pin "P$22") (pinfunction "SFB_P$22") (pintype "bidirectional"))
    )
    (net (code "51") (name "/M1_SENSE") (class "Default")
      (node (ref "C11") (pin "1") (pinfunction "1_1") (pintype "passive"))
      (node (ref "IC3") (pin "36") (pinfunction "PB1_36") (pintype "bidirectional"))
      (node (ref "R9") (pin "2") (pinfunction "2_2") (pintype "passive"))
      (node (ref "U1") (pin "P$24") (pinfunction "FBB_P$24") (pintype "bidirectional"))
    )
    (net (code "52") (name "/MPOWER") (class "Default")
      (node (ref "C26") (pin "1") (pinfunction "1_1") (pintype "passive"))
      (node (ref "C28") (pin "1") (pinfunction "1_1") (pintype "passive"))
      (node (ref "C31") (pin "1") (pinfunction "1_1") (pintype "passive"))
      (node (ref "C8") (pin "1") (pinfunction "1_1") (pintype "passive"))
      (node (ref "C9") (pin "2") (pinfunction "2_2") (pintype "passive"))
      (node (ref "Q5") (pin "10") (pinfunction "D2_10") (pintype "bidirectional"))
      (node (ref "Q5") (pin "5") (pinfunction "D2_5") (pintype "bidirectional"))
      (node (ref "Q5") (pin "6") (pinfunction "D2_6") (pintype "bidirectional"))
      (node (ref "R10") (pin "2") (pinfunction "2_2") (pintype "passive"))
      (node (ref "R18") (pin "1") (pinfunction "1_1") (pintype "passive"))
      (node (ref "R34") (pin "2") (pinfunction "2_2") (pintype "passive"))
      (node (ref "U1") (pin "P$17") (pinfunction "VPWRB_1_P$17") (pintype "bidirectional"))
      (node (ref "U1") (pin "P$18") (pinfunction "VPWRB_2_P$18") (pintype "bidirectional"))
      (node (ref "U1") (pin "P$26") (pinfunction "VPWRB_3_P$26") (pintype "bidirectional"))
      (node (ref "U1") (pin "P$27") (pinfunction "VPWRB_4_P$27") (pintype "bidirectional"))
      (node (ref "U1") (pin "P$28") (pinfunction "VPWRB_5_P$28") (pintype "bidirectional"))
      (node (ref "U1") (pin "P$39") (pinfunction "VPWRA_4_P$39") (pintype "bidirectional"))
      (node (ref "U1") (pin "P$4") (pinfunction "VPWRA_1_P$4") (pintype "bidirectional"))
      (node (ref "U1") (pin "P$40") (pinfunction "VPWRA_5_P$40") (pintype "bidirectional"))
      (node (ref "U1") (pin "P$5") (pinfunction "VPWRA_2_P$5") (pintype "bidirectional"))
      (node (ref "U1") (pin "P$6") (pinfunction "VPWRA_3_P$6") (pintype "bidirectional"))
      (node (ref "U2") (pin "4") (pinfunction "VIN_4") (pintype "bidirectional"))
      (node (ref "U2") (pin "5") (pinfunction "VIN_5") (pintype "bidirectional"))
      (node (ref "U2") (pin "6") (pinfunction "VIN_6") (pintype "bidirectional"))
    )
    (net (code "53") (name "/M_STANDBY") (class "Default")
      (node (ref "IC3") (pin "37") (pinfunction "PB2_37") (pintype "bidirectional"))
      (node (ref "R43") (pin "2") (pinfunction "2_2") (pintype "passive"))
      (node (ref "U1") (pin "P$25") (pinfunction "EN_D4_P$25") (pintype "bidirectional"))
      (node (ref "U1") (pin "P$3") (pinfunction "EN_D2_P$3") (pintype "bidirectional"))
    )
    (net (code "54") (name "/OUT1") (class "Default")
      (node (ref "LED6") (pin "2") (pinfunction "2_2") (pintype "passive"))
      (node (ref "LED6") (pin "3") (pinfunction "3_3") (pintype "passive"))
      (node (ref "MOTOR0") (pin "L") (pinfunction "L_L") (pintype "bidirectional"))
      (node (ref "U1") (pin "P$7") (pinfunction "OUT1_1_P$7") (pintype "bidirectional"))
      (node (ref "U1") (pin "P$8") (pinfunction "OUT1_2_P$8") (pintype "bidirectional"))
      (node (ref "U1") (pin "P$9") (pinfunction "OUT1_3_P$9") (pintype "bidirectional"))
    )
    (net (code "55") (name "/OUT2") (class "Default")
      (node (ref "MOTOR0") (pin "R") (pinfunction "R_R") (pintype "bidirectional"))
      (node (ref "R37") (pin "1") (pinfunction "1_1") (pintype "passive"))
      (node (ref "U1") (pin "P$36") (pinfunction "OUT2_1_P$36") (pintype "bidirectional"))
      (node (ref "U1") (pin "P$37") (pinfunction "OUT2_2_P$37") (pintype "bidirectional"))
      (node (ref "U1") (pin "P$38") (pinfunction "OUT2_3_P$38") (pintype "bidirectional"))
    )
    (net (code "56") (name "/OUT3") (class "Default")
      (node (ref "LED7") (pin "2") (pinfunction "2_2") (pintype "passive"))
      (node (ref "LED7") (pin "3") (pinfunction "3_3") (pintype "passive"))
      (node (ref "MOTOR1") (pin "L") (pinfunction "L_L") (pintype "bidirectional"))
      (node (ref "U1") (pin "P$29") (pinfunction "OUT3_1_P$29") (pintype "bidirectional"))
      (node (ref "U1") (pin "P$30") (pinfunction "OUT3_2_P$30") (pintype "bidirectional"))
      (node (ref "U1") (pin "P$31") (pinfunction "OUT3_3_P$31") (pintype "bidirectional"))
    )
    (net (code "57") (name "/OUT4") (class "Default")
      (node (ref "MOTOR1") (pin "R") (pinfunction "R_R") (pintype "bidirectional"))
      (node (ref "R38") (pin "1") (pinfunction "1_1") (pintype "passive"))
      (node (ref "U1") (pin "P$14") (pinfunction "OUT4_1_P$14") (pintype "bidirectional"))
      (node (ref "U1") (pin "P$15") (pinfunction "OUT4_2_P$15") (pintype "bidirectional"))
      (node (ref "U1") (pin "P$16") (pinfunction "OUT4_3_P$16") (pintype "bidirectional"))
    )
    (net (code "58") (name "/RAW_SPWR") (class "Default")
      (node (ref "C27") (pin "1") (pinfunction "1_1") (pintype "passive"))
      (node (ref "Q4") (pin "10") (pinfunction "D2_10") (pintype "bidirectional"))
      (node (ref "Q4") (pin "2") (pinfunction "G1_2") (pintype "bidirectional"))
      (node (ref "Q4") (pin "5") (pinfunction "D2_5") (pintype "bidirectional"))
      (node (ref "Q4") (pin "6") (pinfunction "D2_6") (pintype "bidirectional"))
      (node (ref "R29") (pin "1") (pinfunction "1_1") (pintype "passive"))
      (node (ref "R36") (pin "2") (pinfunction "2_2") (pintype "passive"))
      (node (ref "SERVO_PWR") (pin "L") (pinfunction "L_L") (pintype "bidirectional"))
    )
    (net (code "59") (name "/RESET") (class "Default")
      (node (ref "C30") (pin "2") (pinfunction "2_2") (pintype "passive"))
      (node (ref "IC3") (pin "14") (pinfunction "NRST_14") (pintype "input"))
      (node (ref "JP1") (pin "5") (pinfunction "5_5") (pintype "passive"))
      (node (ref "R7") (pin "1") (pinfunction "1_1") (pintype "passive"))
      (node (ref "RESET") (pin "1") (pinfunction "S_1") (pintype "passive"))
      (node (ref "RESET") (pin "2") (pinfunction "S1_2") (pintype "passive"))
    )
    (net (code "60") (name "/SERVO0") (class "Default")
      (node (ref "IC3") (pin "59") (pinfunction "PD12_59") (pintype "bidirectional"))
      (node (ref "J16") (pin "8") (pinfunction "8_8") (pintype "passive"))
    )
    (net (code "61") (name "/SERVO1") (class "Default")
      (node (ref "IC3") (pin "60") (pinfunction "PD13_60") (pintype "bidirectional"))
      (node (ref "J16") (pin "7") (pinfunction "7_7") (pintype "passive"))
    )
    (net (code "62") (name "/SERVO2") (class "Default")
      (node (ref "IC3") (pin "61") (pinfunction "PD14_61") (pintype "bidirectional"))
      (node (ref "J16") (pin "6") (pinfunction "6_6") (pintype "passive"))
    )
    (net (code "63") (name "/SERVO3") (class "Default")
      (node (ref "IC3") (pin "62") (pinfunction "PD15_62") (pintype "bidirectional"))
      (node (ref "J16") (pin "5") (pinfunction "5_5") (pintype "passive"))
    )
    (net (code "64") (name "/SERVO4") (class "Default")
      (node (ref "IC3") (pin "63") (pinfunction "PC6_63") (pintype "bidirectional"))
      (node (ref "J16") (pin "4") (pinfunction "4_4") (pintype "passive"))
    )
    (net (code "65") (name "/SERVO5") (class "Default")
      (node (ref "IC3") (pin "64") (pinfunction "PC7_64") (pintype "bidirectional"))
      (node (ref "J16") (pin "3") (pinfunction "3_3") (pintype "passive"))
    )
    (net (code "66") (name "/SERVO6") (class "Default")
      (node (ref "IC3") (pin "65") (pinfunction "PC8_65") (pintype "bidirectional"))
      (node (ref "J16") (pin "2") (pinfunction "2_2") (pintype "passive"))
    )
    (net (code "67") (name "/SERVO7") (class "Default")
      (node (ref "IC3") (pin "66") (pinfunction "PC9_66") (pintype "bidirectional"))
      (node (ref "J16") (pin "1") (pinfunction "1_1") (pintype "passive"))
    )
    (net (code "68") (name "/SERVO_SENSE") (class "Default")
      (node (ref "IC3") (pin "34") (pinfunction "PC5_34") (pintype "bidirectional"))
      (node (ref "R40") (pin "2") (pinfunction "2_2") (pintype "passive"))
      (node (ref "R41") (pin "1") (pinfunction "1_1") (pintype "passive"))
    )
    (net (code "69") (name "/SPI1_MISO") (class "Default")
      (node (ref "IC3") (pin "31") (pinfunction "PA6_31") (pintype "bidirectional"))
      (node (ref "J5") (pin "4") (pinfunction "4_4") (pintype "passive"))
    )
    (net (code "70") (name "/SPI1_MOSI") (class "Default")
      (node (ref "IC3") (pin "32") (pinfunction "PA7_32") (pintype "bidirectional"))
      (node (ref "J5") (pin "3") (pinfunction "3_3") (pintype "passive"))
    )
    (net (code "71") (name "/SPI1_NSS") (class "Default")
      (node (ref "IC3") (pin "77") (pinfunction "PA15_77") (pintype "bidirectional"))
      (node (ref "J5") (pin "6") (pinfunction "6_6") (pintype "passive"))
    )
    (net (code "72") (name "/SPI1_SCK") (class "Default")
      (node (ref "IC3") (pin "30") (pinfunction "PA5_30") (pintype "bidirectional"))
      (node (ref "J5") (pin "5") (pinfunction "5_5") (pintype "passive"))
    )
    (net (code "73") (name "/SPI3_MISO") (class "Default")
      (node (ref "IC3") (pin "79") (pinfunction "PC11_79") (pintype "bidirectional"))
      (node (ref "SD") (pin "7") (pinfunction "DO_7") (pintype "bidirectional"))
    )
    (net (code "74") (name "/SPI3_MOSI") (class "Default")
      (node (ref "IC3") (pin "80") (pinfunction "PC12_80") (pintype "bidirectional"))
      (node (ref "SD") (pin "3") (pinfunction "DI_3") (pintype "bidirectional"))
    )
    (net (code "75") (name "/SPI3_NSS") (class "Default")
      (node (ref "IC3") (pin "83") (pinfunction "PD2_83") (pintype "bidirectional"))
      (node (ref "SD") (pin "2") (pinfunction "CS_2") (pintype "bidirectional"))
    )
    (net (code "76") (name "/SPI3_SCK") (class "Default")
      (node (ref "IC3") (pin "78") (pinfunction "PC10_78") (pintype "bidirectional"))
      (node (ref "SD") (pin "5") (pinfunction "SCK_5") (pintype "bidirectional"))
    )
    (net (code "77") (name "/SPWR") (class "Default")
      (node (ref "J15") (pin "1") (pinfunction "1_1") (pintype "passive"))
      (node (ref "J15") (pin "2") (pinfunction "2_2") (pintype "passive"))
      (node (ref "J15") (pin "3") (pinfunction "3_3") (pintype "passive"))
      (node (ref "J15") (pin "4") (pinfunction "4_4") (pintype "passive"))
      (node (ref "J15") (pin "5") (pinfunction "5_5") (pintype "passive"))
      (node (ref "J15") (pin "6") (pinfunction "6_6") (pintype "passive"))
      (node (ref "J15") (pin "7") (pinfunction "7_7") (pintype "passive"))
      (node (ref "J15") (pin "8") (pinfunction "8_8") (pintype "passive"))
      (node (ref "Q4") (pin "1") (pinfunction "S1_1") (pintype "bidirectional"))
      (node (ref "Q4") (pin "3") (pinfunction "S2_3") (pintype "bidirectional"))
      (node (ref "R40") (pin "1") (pinfunction "1_1") (pintype "passive"))
    )
    (net (code "78") (name "/SWDCLK") (class "Default")
      (node (ref "IC3") (pin "76") (pinfunction "PA14_76") (pintype "bidirectional"))
      (node (ref "J7") (pin "2") (pinfunction "2_2") (pintype "passive"))
    )
    (net (code "79") (name "/SWDIO") (class "Default")
      (node (ref "IC3") (pin "72") (pinfunction "PA13_72") (pintype "bidirectional"))
      (node (ref "J7") (pin "1") (pinfunction "1_1") (pintype "passive"))
    )
    (net (code "80") (name "/USART1_RX") (class "Default")
      (node (ref "IC3") (pin "93") (pinfunction "PB7_93") (pintype "bidirectional"))
      (node (ref "J6") (pin "3") (pinfunction "3_3") (pintype "passive"))
    )
    (net (code "81") (name "/USART1_TX") (class "Default")
      (node (ref "IC3") (pin "92") (pinfunction "PB6_92") (pintype "bidirectional"))
      (node (ref "J6") (pin "2") (pinfunction "2_2") (pintype "passive"))
    )
    (net (code "82") (name "/USART2_RX") (class "Default")
      (node (ref "IC3") (pin "87") (pinfunction "PD6_87") (pintype "bidirectional"))
      (node (ref "J3") (pin "2") (pinfunction "2_2") (pintype "passive"))
    )
    (net (code "83") (name "/USART2_TX") (class "Default")
      (node (ref "IC3") (pin "86") (pinfunction "PD5_86") (pintype "bidirectional"))
      (node (ref "J3") (pin "1") (pinfunction "1_1") (pintype "passive"))
    )
    (net (code "84") (name "/USB_5V") (class "Default")
      (node (ref "C22") (pin "2") (pinfunction "2_2") (pintype "passive"))
      (node (ref "C24") (pin "2") (pinfunction "2_2") (pintype "passive"))
      (node (ref "IC3") (pin "68") (pinfunction "PA9_68") (pintype "bidirectional"))
      (node (ref "Q1") (pin "3") (pinfunction "D_3") (pintype "passive"))
      (node (ref "USB2") (pin "VBUS") (pinfunction "VBUS_VBUS") (pintype "bidirectional"))
    )
    (net (code "85") (name "/USB_DEV_DM") (class "Default")
      (node (ref "C14") (pin "1") (pinfunction "1_1") (pintype "passive"))
      (node (ref "IC3") (pin "70") (pinfunction "PA11_70") (pintype "bidirectional"))
      (node (ref "R46") (pin "2") (pinfunction "2_2") (pintype "passive"))
    )
    (net (code "86") (name "/USB_DEV_DP") (class "Default")
      (node (ref "C13") (pin "1") (pinfunction "1_1") (pintype "passive"))
      (node (ref "IC3") (pin "71") (pinfunction "PA12_71") (pintype "bidirectional"))
      (node (ref "R47") (pin "2") (pinfunction "2_2") (pintype "passive"))
    )
    (net (code "87") (name "/USB_HOST_DM") (class "Default")
      (node (ref "C18") (pin "1") (pinfunction "1_1") (pintype "passive"))
      (node (ref "IC3") (pin "53") (pinfunction "PB14_53") (pintype "bidirectional"))
      (node (ref "R49") (pin "2") (pinfunction "2_2") (pintype "passive"))
    )
    (net (code "88") (name "/USB_HOST_DP") (class "Default")
      (node (ref "C17") (pin "1") (pinfunction "1_1") (pintype "passive"))
      (node (ref "IC3") (pin "54") (pinfunction "PB15_54") (pintype "bidirectional"))
      (node (ref "R48") (pin "2") (pinfunction "2_2") (pintype "passive"))
    )
    (net (code "89") (name "/USB_HOST_EN") (class "Default")
      (node (ref "IC3") (pin "52") (pinfunction "PB13_52") (pintype "bidirectional"))
      (node (ref "U$2") (pin "4") (pinfunction "EN_4") (pintype "bidirectional"))
    )
    (net (code "90") (name "/USB_HOST_FAULT") (class "Default")
      (node (ref "IC3") (pin "51") (pinfunction "PB12_51") (pintype "bidirectional"))
      (node (ref "U$2") (pin "5") (pinfunction "FAULT_5") (pintype "bidirectional"))
    )
    (net (code "91") (name "GND") (class "Default")
      (node (ref "BTN0") (pin "3") (pinfunction "P_3") (pintype "passive"))
      (node (ref "BTN0") (pin "4") (pinfunction "P1_4") (pintype "passive"))
      (node (ref "BTN1") (pin "3") (pinfunction "P_3") (pintype "passive"))
      (node (ref "BTN1") (pin "4") (pinfunction "P1_4") (pintype "passive"))
      (node (ref "C1") (pin "2") (pinfunction "2_2") (pintype "passive"))
      (node (ref "C10") (pin "2") (pinfunction "2_2") (pintype "passive"))
      (node (ref "C11") (pin "2") (pinfunction "2_2") (pintype "passive"))
      (node (ref "C12") (pin "2") (pinfunction "2_2") (pintype "passive"))
      (node (ref "C13") (pin "2") (pinfunction "2_2") (pintype "passive"))
      (node (ref "C14") (pin "2") (pinfunction "2_2") (pintype "passive"))
      (node (ref "C15") (pin "2") (pinfunction "2_2") (pintype "passive"))
      (node (ref "C16") (pin "2") (pinfunction "2_2") (pintype "passive"))
      (node (ref "C17") (pin "2") (pinfunction "2_2") (pintype "passive"))
      (node (ref "C18") (pin "2") (pinfunction "2_2") (pintype "passive"))
      (node (ref "C19") (pin "2") (pinfunction "2_2") (pintype "passive"))
      (node (ref "C2") (pin "2") (pinfunction "2_2") (pintype "passive"))
      (node (ref "C21") (pin "2") (pinfunction "2_2") (pintype "passive"))
      (node (ref "C22") (pin "1") (pinfunction "1_1") (pintype "passive"))
      (node (ref "C23") (pin "2") (pinfunction "2_2") (pintype "passive"))
      (node (ref "C24") (pin "1") (pinfunction "1_1") (pintype "passive"))
      (node (ref "C25") (pin "2") (pinfunction "2_2") (pintype "passive"))
      (node (ref "C26") (pin "2") (pinfunction "2_2") (pintype "passive"))
      (node (ref "C27") (pin "2") (pinfunction "2_2") (pintype "passive"))
      (node (ref "C28") (pin "2") (pinfunction "2_2") (pintype "passive"))
      (node (ref "C3") (pin "2") (pinfunction "2_2") (pintype "passive"))
      (node (ref "C31") (pin "2") (pinfunction "2_2") (pintype "passive"))
      (node (ref "C33") (pin "1") (pinfunction "1_1") (pintype "passive"))
      (node (ref "C34") (pin "2") (pinfunction "2_2") (pintype "passive"))
      (node (ref "C35") (pin "2") (pinfunction "2_2") (pintype "passive"))
      (node (ref "C36") (pin "2") (pinfunction "2_2") (pintype "passive"))
      (node (ref "C37") (pin "2") (pinfunction "2_2") (pintype "passive"))
      (node (ref "C39") (pin "2") (pinfunction "2_2") (pintype "passive"))
      (node (ref "C4") (pin "2") (pinfunction "2_2") (pintype "passive"))
      (node (ref "C40") (pin "2") (pinfunction "2_2") (pintype "passive"))
      (node (ref "C41") (pin "2") (pinfunction "2_2") (pintype "passive"))
      (node (ref "C42") (pin "2") (pinfunction "2_2") (pintype "passive"))
      (node (ref "C43") (pin "2") (pinfunction "2_2") (pintype "passive"))
      (node (ref "C44") (pin "-") (pinfunction "-_-") (pintype "passive"))
      (node (ref "C46") (pin "2") (pinfunction "2_2") (pintype "passive"))
      (node (ref "C47") (pin "2") (pinfunction "2_2") (pintype "passive"))
      (node (ref "C5") (pin "2") (pinfunction "2_2") (pintype "passive"))
      (node (ref "C6") (pin "2") (pinfunction "2_2") (pintype "passive"))
      (node (ref "C7") (pin "2") (pinfunction "2_2") (pintype "passive"))
      (node (ref "IC3") (pin "10") (pinfunction "VSS_5_10") (pintype "power_in"))
      (node (ref "IC3") (pin "20") (pinfunction "VSSA_20") (pintype "power_in"))
      (node (ref "IC3") (pin "27") (pinfunction "VSS_4_27") (pintype "power_in"))
      (node (ref "IC3") (pin "74") (pinfunction "VSS_2_74") (pintype "power_in"))
      (node (ref "IC3") (pin "99") (pinfunction "VSS_6_99") (pintype "power_in"))
      (node (ref "IC4") (pin "4") (pinfunction "V-_4") (pintype "power_in"))
      (node (ref "J1") (pin "3") (pinfunction "3_3") (pintype "passive"))
      (node (ref "J11") (pin "1") (pinfunction "1_1") (pintype "passive"))
      (node (ref "J11") (pin "10") (pinfunction "10_10") (pintype "passive"))
      (node (ref "J11") (pin "11") (pinfunction "11_11") (pintype "passive"))
      (node (ref "J11") (pin "12") (pinfunction "12_12") (pintype "passive"))
      (node (ref "J11") (pin "13") (pinfunction "13_13") (pintype "passive"))
      (node (ref "J11") (pin "14") (pinfunction "14_14") (pintype "passive"))
      (node (ref "J11") (pin "15") (pinfunction "15_15") (pintype "passive"))
      (node (ref "J11") (pin "2") (pinfunction "2_2") (pintype "passive"))
      (node (ref "J11") (pin "3") (pinfunction "3_3") (pintype "passive"))
      (node (ref "J11") (pin "4") (pinfunction "4_4") (pintype "passive"))
      (node (ref "J11") (pin "5") (pinfunction "5_5") (pintype "passive"))
      (node (ref "J11") (pin "6") (pinfunction "6_6") (pintype "passive"))
      (node (ref "J11") (pin "7") (pinfunction "7_7") (pintype "passive"))
      (node (ref "J11") (pin "8") (pinfunction "8_8") (pintype "passive"))
      (node (ref "J11") (pin "9") (pinfunction "9_9") (pintype "passive"))
      (node (ref "J14") (pin "1") (pinfunction "1_1") (pintype "passive"))
      (node (ref "J14") (pin "2") (pinfunction "2_2") (pintype "passive"))
      (node (ref "J14") (pin "3") (pinfunction "3_3") (pintype "passive"))
      (node (ref "J14") (pin "4") (pinfunction "4_4") (pintype "passive"))
      (node (ref "J14") (pin "5") (pinfunction "5_5") (pintype "passive"))
      (node (ref "J14") (pin "6") (pinfunction "6_6") (pintype "passive"))
      (node (ref "J14") (pin "7") (pinfunction "7_7") (pintype "passive"))
      (node (ref "J14") (pin "8") (pinfunction "8_8") (pintype "passive"))
      (node (ref "J2") (pin "3") (pinfunction "3_3") (pintype "passive"))
      (node (ref "J3") (pin "3") (pinfunction "3_3") (pintype "passive"))
      (node (ref "J4") (pin "3") (pinfunction "3_3") (pintype "passive"))
      (node (ref "J5") (pin "2") (pinfunction "2_2") (pintype "passive"))
      (node (ref "J6") (pin "4") (pinfunction "4_4") (pintype "passive"))
      (node (ref "J7") (pin "3") (pinfunction "3_3") (pintype "passive"))
      (node (ref "J8") (pin "1") (pinfunction "1_1") (pintype "passive"))
      (node (ref "J8") (pin "2") (pinfunction "2_2") (pintype "passive"))
      (node (ref "J8") (pin "3") (pinfunction "3_3") (pintype "passive"))
      (node (ref "J8") (pin "4") (pinfunction "4_4") (pintype "passive"))
      (node (ref "J8") (pin "5") (pinfunction "5_5") (pintype "passive"))
      (node (ref "J8") (pin "6") (pinfunction "6_6") (pintype "passive"))
      (node (ref "J8") (pin "7") (pinfunction "7_7") (pintype "passive"))
      (node (ref "J8") (pin "8") (pinfunction "8_8") (pintype "passive"))
      (node (ref "JP1") (pin "6") (pinfunction "6_6") (pintype "passive"))
      (node (ref "LCD") (pin "K") (pinfunction "K_K") (pintype "bidirectional"))
      (node (ref "LCD") (pin "R/W") (pinfunction "R/W_R/W") (pintype "bidirectional"))
      (node (ref "LCD") (pin "VSS") (pinfunction "VSS_VSS") (pintype "bidirectional"))
      (node (ref "LED2") (pin "C") (pinfunction "C_C") (pintype "passive"))
      (node (ref "LED3") (pin "C") (pinfunction "C_C") (pintype "passive"))
      (node (ref "LED4") (pin "C") (pinfunction "C_C") (pintype "passive"))
      (node (ref "POT") (pin "3") (pinfunction "E_3") (pintype "passive"))
      (node (ref "POWER") (pin "R") (pinfunction "R_R") (pintype "bidirectional"))
      (node (ref "Q2") (pin "2") (pinfunction "E_2") (pintype "passive"))
      (node (ref "Q3") (pin "1") (pinfunction "S_1") (pintype "bidirectional"))
      (node (ref "Q3") (pin "2") (pinfunction "S_2") (pintype "bidirectional"))
      (node (ref "Q3") (pin "3") (pinfunction "S_3") (pintype "bidirectional"))
      (node (ref "R11") (pin "1") (pinfunction "1_1") (pintype "passive"))
      (node (ref "R19") (pin "2") (pinfunction "2_2") (pintype "passive"))
      (node (ref "R2") (pin "2") (pinfunction "2_2") (pintype "passive"))
      (node (ref "R26") (pin "1") (pinfunction "1_1") (pintype "passive"))
      (node (ref "R28") (pin "2") (pinfunction "2_2") (pintype "passive"))
      (node (ref "R33") (pin "1") (pinfunction "1_1") (pintype "passive"))
      (node (ref "R35") (pin "1") (pinfunction "1_1") (pintype "passive"))
      (node (ref "R41") (pin "2") (pinfunction "2_2") (pintype "passive"))
      (node (ref "R42") (pin "1") (pinfunction "1_1") (pintype "passive"))
      (node (ref "R43") (pin "1") (pinfunction "1_1") (pintype "passive"))
      (node (ref "R44") (pin "1") (pinfunction "1_1") (pintype "passive"))
      (node (ref "R8") (pin "1") (pinfunction "1_1") (pintype "passive"))
      (node (ref "R9") (pin "1") (pinfunction "1_1") (pintype "passive"))
      (node (ref "RESET") (pin "3") (pinfunction "P_3") (pintype "passive"))
      (node (ref "RESET") (pin "4") (pinfunction "P1_4") (pintype "passive"))
      (node (ref "SD") (pin "6") (pinfunction "GND_6") (pintype "bidirectional"))
      (node (ref "SD") (pin "CD1") (pinfunction "SHIELD_CD1") (pintype "bidirectional"))
      (node (ref "SD") (pin "CD2") (pinfunction "SHIELD_CD2") (pintype "bidirectional"))
      (node (ref "SD") (pin "GND1") (pinfunction "SHIELD_GND1") (pintype "bidirectional"))
      (node (ref "SD") (pin "GND3") (pinfunction "SHIELD_GND3") (pintype "bidirectional"))
      (node (ref "SERVO_PWR") (pin "R") (pinfunction "R_R") (pintype "bidirectional"))
      (node (ref "SW1") (pin "P$2") (pinfunction "P$2_P$2") (pintype "bidirectional"))
      (node (ref "U$1") (pin "1") (pinfunction "GND_1") (pintype "bidirectional"))
      (node (ref "U$1") (pin "2") (pinfunction "GND_2") (pintype "bidirectional"))
      (node (ref "U$1") (pin "26") (pinfunction "SA0_26") (pintype "bidirectional"))
      (node (ref "U$1") (pin "27") (pinfunction "SA0_27") (pintype "bidirectional"))
      (node (ref "U$1") (pin "3") (pinfunction "GND_3") (pintype "bidirectional"))
      (node (ref "U$1") (pin "4") (pinfunction "GND_4") (pintype "bidirectional"))
      (node (ref "U$1") (pin "5") (pinfunction "GND_5") (pintype "bidirectional"))
      (node (ref "U$1") (pin "6") (pinfunction "GND_6") (pintype "bidirectional"))
      (node (ref "U$2") (pin "1") (pinfunction "GND_1") (pintype "bidirectional"))
      (node (ref "U$3") (pin "7") (pinfunction "GND_7") (pintype "bidirectional"))
      (node (ref "U1") (pin "P$10") (pinfunction "PGNDA_1_P$10") (pintype "bidirectional"))
      (node (ref "U1") (pin "P$11") (pinfunction "PGNDA_2_P$11") (pintype "bidirectional"))
      (node (ref "U1") (pin "P$12") (pinfunction "PGNDB_1_P$12") (pintype "bidirectional"))
      (node (ref "U1") (pin "P$13") (pinfunction "PGNDB_2_P$13") (pintype "bidirectional"))
      (node (ref "U1") (pin "P$32") (pinfunction "PGNDB_3_P$32") (pintype "bidirectional"))
      (node (ref "U1") (pin "P$33") (pinfunction "PGNDB_4_P$33") (pintype "bidirectional"))
      (node (ref "U1") (pin "P$34") (pinfunction "PGNDA_3_P$34") (pintype "bidirectional"))
      (node (ref "U1") (pin "P$35") (pinfunction "PGNDA_4_P$35") (pintype "bidirectional"))
      (node (ref "U1") (pin "P$45") (pinfunction "GND_P$45") (pintype "bidirectional"))
      (node (ref "U1") (pin "P$46") (pinfunction "GND_P$46") (pintype "bidirectional"))
      (node (ref "U1") (pin "P$47") (pinfunction "GND_P$47") (pintype "bidirectional"))
      (node (ref "U2") (pin "14") (pinfunction "GND_14") (pintype "bidirectional"))
      (node (ref "U2") (pin "P$1") (pinfunction "GND_P$1") (pintype "bidirectional"))
      (node (ref "U3") (pin "3") (pinfunction "GND_3") (pintype "bidirectional"))
      (node (ref "U6") (pin "P$2") (pinfunction "GND_P$2") (pintype "bidirectional"))
      (node (ref "U8") (pin "P$2") (pinfunction "GND_P$2") (pintype "bidirectional"))
      (node (ref "USB1") (pin "GND") (pinfunction "GND_GND") (pintype "bidirectional"))
      (node (ref "USB1") (pin "GND@1") (pinfunction "GND_GND@1") (pintype "bidirectional"))
      (node (ref "USB1") (pin "GND@2") (pinfunction "GND_GND@2") (pintype "bidirectional"))
      (node (ref "USB2") (pin "GND") (pinfunction "GND_GND") (pintype "bidirectional"))
      (node (ref "USB2") (pin "MTN1") (pinfunction "MTN2_MTN1") (pintype "bidirectional"))
      (node (ref "USB2") (pin "MTN2") (pinfunction "MTN3_MTN2") (pintype "bidirectional"))
      (node (ref "USB2") (pin "MTN3") (pinfunction "MTN1_MTN3") (pintype "bidirectional"))
      (node (ref "USB2") (pin "MTN4") (pinfunction "MTN4_MTN4") (pintype "bidirectional"))
      (node (ref "XB1") (pin "10") (pinfunction "GND_10") (pintype "power_in"))
    )
    (net (code "92") (name "Net-(AP1084-ADJ)") (class "Default")
      (node (ref "AP1084") (pin "1") (pinfunction "ADJ_1") (pintype "bidirectional"))
      (node (ref "C38") (pin "2") (pinfunction "2_2") (pintype "passive"))
      (node (ref "R44") (pin "2") (pinfunction "2_2") (pintype "passive"))
      (node (ref "R45") (pin "1") (pinfunction "1_1") (pintype "passive"))
    )
    (net (code "93") (name "Net-(C21-Pad1)") (class "Default")
      (node (ref "C21") (pin "1") (pinfunction "1_1") (pintype "passive"))
      (node (ref "C23") (pin "1") (pinfunction "1_1") (pintype "passive"))
      (node (ref "U$2") (pin "6") (pinfunction "VOUT_6") (pintype "bidirectional"))
      (node (ref "U$2") (pin "7") (pinfunction "VOUT_7") (pintype "bidirectional"))
      (node (ref "U$2") (pin "8") (pinfunction "VOUT_8") (pintype "bidirectional"))
      (node (ref "USB1") (pin "VBUS") (pinfunction "VBUS_VBUS") (pintype "bidirectional"))
    )
    (net (code "94") (name "Net-(IC3A-VCAP_2)") (class "Default")
      (node (ref "C37") (pin "1") (pinfunction "1_1") (pintype "passive"))
      (node (ref "IC3") (pin "73") (pinfunction "VCAP_2_73") (pintype "power_in"))
    )
    (net (code "95") (name "Net-(IC3B-OSC_IN)") (class "Default")
      (node (ref "C19") (pin "1") (pinfunction "1_1") (pintype "passive"))
      (node (ref "IC3") (pin "12") (pinfunction "OSC_IN_12") (pintype "input"))
      (node (ref "Y2") (pin "2") (pinfunction "2_2") (pintype "passive"))
    )
    (net (code "96") (name "Net-(IC3B-OSC_OUT)") (class "Default")
      (node (ref "C2") (pin "1") (pinfunction "1_1") (pintype "passive"))
      (node (ref "IC3") (pin "13") (pinfunction "OSC_OUT_13") (pintype "output"))
      (node (ref "Y2") (pin "1") (pinfunction "1_1") (pintype "passive"))
    )
    (net (code "97") (name "Net-(IC3M-VCAP_1)") (class "Default")
      (node (ref "C7") (pin "1") (pinfunction "1_1") (pintype "passive"))
      (node (ref "IC3") (pin "49") (pinfunction "VCAP_1_49") (pintype "power_in"))
    )
    (net (code "98") (name "Net-(IC3N-BOOT0)") (class "Default")
      (node (ref "IC3") (pin "94") (pinfunction "BOOT0_94") (pintype "input"))
      (node (ref "R42") (pin "2") (pinfunction "2_2") (pintype "passive"))
    )
    (net (code "99") (name "Net-(IC4A-+IN)") (class "Default")
      (node (ref "IC4") (pin "3") (pinfunction "+IN_3") (pintype "input"))
      (node (ref "R10") (pin "1") (pinfunction "1_1") (pintype "passive"))
      (node (ref "R11") (pin "2") (pinfunction "2_2") (pintype "passive"))
    )
    (net (code "100") (name "Net-(IC4A-OUT)") (class "Default")
      (node (ref "IC4") (pin "1") (pinfunction "OUT_1") (pintype "output"))
      (node (ref "Q1") (pin "1") (pinfunction "G_1") (pintype "passive"))
    )
    (net (code "101") (name "Net-(IC4B-+IN)") (class "Default")
      (node (ref "IC4") (pin "5") (pinfunction "+IN_5") (pintype "input"))
      (node (ref "R28") (pin "1") (pinfunction "1_1") (pintype "passive"))
      (node (ref "R29") (pin "2") (pinfunction "2_2") (pintype "passive"))
    )
    (net (code "102") (name "Net-(IC4B--IN)") (class "Default")
      (node (ref "IC4") (pin "6") (pinfunction "-IN_6") (pintype "input"))
      (node (ref "R26") (pin "2") (pinfunction "2_2") (pintype "passive"))
      (node (ref "R27") (pin "1") (pinfunction "1_1") (pintype "passive"))
    )
    (net (code "103") (name "Net-(IC4B-OUT)") (class "Default")
      (node (ref "IC4") (pin "7") (pinfunction "OUT_7") (pintype "output"))
      (node (ref "R36") (pin "1") (pinfunction "1_1") (pintype "passive"))
      (node (ref "U3") (pin "2") (pinfunction "A_2") (pintype "bidirectional"))
    )
    (net (code "104") (name "Net-(J12-Pad1)") (class "Default")
      (node (ref "J12") (pin "1") (pinfunction "1_1") (pintype "passive"))
      (node (ref "J12") (pin "10") (pinfunction "10_10") (pintype "passive"))
      (node (ref "J12") (pin "11") (pinfunction "11_11") (pintype "passive"))
      (node (ref "J12") (pin "12") (pinfunction "12_12") (pintype "passive"))
      (node (ref "J12") (pin "13") (pinfunction "13_13") (pintype "passive"))
      (node (ref "J12") (pin "14") (pinfunction "14_14") (pintype "passive"))
      (node (ref "J12") (pin "15") (pinfunction "15_15") (pintype "passive"))
      (node (ref "J12") (pin "2") (pinfunction "2_2") (pintype "passive"))
      (node (ref "J12") (pin "3") (pinfunction "3_3") (pintype "passive"))
      (node (ref "J12") (pin "4") (pinfunction "4_4") (pintype "passive"))
      (node (ref "J12") (pin "5") (pinfunction "5_5") (pintype "passive"))
      (node (ref "J12") (pin "6") (pinfunction "6_6") (pintype "passive"))
      (node (ref "J12") (pin "7") (pinfunction "7_7") (pintype "passive"))
      (node (ref "J12") (pin "8") (pinfunction "8_8") (pintype "passive"))
      (node (ref "J12") (pin "9") (pinfunction "9_9") (pintype "passive"))
      (node (ref "JP2") (pin "2") (pinfunction "2_2") (pintype "passive"))
    )
    (net (code "105") (name "Net-(L1-1)") (class "Default")
      (node (ref "C32") (pin "2") (pinfunction "2_2") (pintype "passive"))
      (node (ref "L1") (pin "P$1") (pinfunction "1_P$1") (pintype "passive"))
      (node (ref "Q3") (pin "5") (pinfunction "D_5") (pintype "bidirectional"))
      (node (ref "Q3") (pin "6") (pinfunction "D_6") (pintype "bidirectional"))
      (node (ref "Q3") (pin "7") (pinfunction "D_7") (pintype "bidirectional"))
      (node (ref "Q3") (pin "8") (pinfunction "D_8") (pintype "bidirectional"))
      (node (ref "U2") (pin "10") (pinfunction "SW_10") (pintype "bidirectional"))
      (node (ref "U2") (pin "8") (pinfunction "SW_8") (pintype "bidirectional"))
      (node (ref "U2") (pin "9") (pinfunction "SW_9") (pintype "bidirectional"))
    )
    (net (code "106") (name "Net-(LCD-PadA)") (class "Default")
      (node (ref "LCD") (pin "A") (pinfunction "A_A") (pintype "bidirectional"))
      (node (ref "R1") (pin "1") (pinfunction "1_1") (pintype "passive"))
    )
    (net (code "107") (name "Net-(LED2-PadA)") (class "Default")
      (node (ref "LED2") (pin "A") (pinfunction "A_A") (pintype "passive"))
      (node (ref "R20") (pin "1") (pinfunction "1_1") (pintype "passive"))
    )
    (net (code "108") (name "Net-(LED3-PadA)") (class "Default")
      (node (ref "LED3") (pin "A") (pinfunction "A_A") (pintype "passive"))
      (node (ref "R21") (pin "1") (pinfunction "1_1") (pintype "passive"))
    )
    (net (code "109") (name "Net-(LED4-PadA)") (class "Default")
      (node (ref "LED4") (pin "A") (pinfunction "A_A") (pintype "passive"))
      (node (ref "R4") (pin "1") (pinfunction "1_1") (pintype "passive"))
    )
    (net (code "110") (name "Net-(LED5-PadC)") (class "Default")
      (node (ref "LED5") (pin "C") (pinfunction "C_C") (pintype "passive"))
      (node (ref "R35") (pin "2") (pinfunction "2_2") (pintype "passive"))
    )
    (net (code "111") (name "Net-(LED6-Pad1)") (class "Default")
      (node (ref "LED6") (pin "1") (pinfunction "1_1") (pintype "passive"))
      (node (ref "LED6") (pin "4") (pinfunction "4_4") (pintype "passive"))
      (node (ref "R37") (pin "2") (pinfunction "2_2") (pintype "passive"))
    )
    (net (code "112") (name "Net-(LED7-Pad1)") (class "Default")
      (node (ref "LED7") (pin "1") (pinfunction "1_1") (pintype "passive"))
      (node (ref "LED7") (pin "4") (pinfunction "4_4") (pintype "passive"))
      (node (ref "R38") (pin "2") (pinfunction "2_2") (pintype "passive"))
    )
    (net (code "113") (name "Net-(POT-S)") (class "Default")
      (node (ref "LCD") (pin "VO") (pinfunction "VO_VO") (pintype "bidirectional"))
      (node (ref "POT") (pin "2") (pinfunction "S_2") (pintype "passive"))
    )
    (net (code "114") (name "Net-(POWER-PadL)") (class "Default")
      (node (ref "POWER") (pin "L") (pinfunction "L_L") (pintype "bidirectional"))
      (node (ref "Q5") (pin "7") (pinfunction "D1_7") (pintype "bidirectional"))
      (node (ref "Q5") (pin "8") (pinfunction "D1_8") (pintype "bidirectional"))
      (node (ref "Q5") (pin "9") (pinfunction "D1_9") (pintype "bidirectional"))
    )
    (net (code "115") (name "Net-(Q1-S)") (class "Default")
      (node (ref "F1") (pin "1") (pinfunction "1_1") (pintype "bidirectional"))
      (node (ref "Q1") (pin "2") (pinfunction "S_2") (pintype "passive"))
    )
    (net (code "116") (name "Net-(Q2-B)") (class "Default")
      (node (ref "Q2") (pin "1") (pinfunction "B_1") (pintype "passive"))
      (node (ref "R39") (pin "2") (pinfunction "2_2") (pintype "passive"))
    )
    (net (code "117") (name "Net-(Q2-C)") (class "Default")
      (node (ref "Q2") (pin "3") (pinfunction "C_3") (pintype "passive"))
      (node (ref "SG1") (pin "-") (pinfunction "2_-") (pintype "passive"))
    )
    (net (code "118") (name "Net-(Q3-G)") (class "Default")
      (node (ref "Q3") (pin "4") (pinfunction "G_4") (pintype "bidirectional"))
      (node (ref "U2") (pin "13") (pinfunction "BG_13") (pintype "bidirectional"))
    )
    (net (code "119") (name "Net-(Q4-G2)") (class "Default")
      (node (ref "Q4") (pin "4") (pinfunction "G2_4") (pintype "bidirectional"))
      (node (ref "U3") (pin "4") (pinfunction "Y_4") (pintype "bidirectional"))
    )
    (net (code "120") (name "Net-(Q5-G1)") (class "Default")
      (node (ref "C29") (pin "2") (pinfunction "2_2") (pintype "passive"))
      (node (ref "Q5") (pin "2") (pinfunction "G1_2") (pintype "bidirectional"))
      (node (ref "R2") (pin "1") (pinfunction "1_1") (pintype "passive"))
      (node (ref "ZD1") (pin "P$1") (pinfunction "A_P$1") (pintype "passive"))
    )
    (net (code "121") (name "Net-(Q5-G2)") (class "Default")
      (node (ref "Q5") (pin "4") (pinfunction "G2_4") (pintype "bidirectional"))
      (node (ref "R3") (pin "1") (pinfunction "1_1") (pintype "passive"))
      (node (ref "R31") (pin "1") (pinfunction "1_1") (pintype "passive"))
      (node (ref "ZD2") (pin "P$1") (pinfunction "A_P$1") (pintype "passive"))
    )
    (net (code "122") (name "Net-(Q5-S1)") (class "Default")
      (node (ref "C29") (pin "1") (pinfunction "1_1") (pintype "passive"))
      (node (ref "Q5") (pin "1") (pinfunction "S1_1") (pintype "bidirectional"))
      (node (ref "Q5") (pin "3") (pinfunction "S2_3") (pintype "bidirectional"))
      (node (ref "R3") (pin "2") (pinfunction "2_2") (pintype "passive"))
      (node (ref "ZD1") (pin "P$2") (pinfunction "C_P$2") (pintype "passive"))
      (node (ref "ZD2") (pin "P$2") (pinfunction "C_P$2") (pintype "passive"))
    )
    (net (code "123") (name "Net-(R31-Pad2)") (class "Default")
      (node (ref "R31") (pin "2") (pinfunction "2_2") (pintype "passive"))
      (node (ref "SW1") (pin "P$1") (pinfunction "P$1_P$1") (pintype "bidirectional"))
    )
    (net (code "124") (name "Net-(U$1-CAP)") (class "Default")
      (node (ref "C35") (pin "1") (pinfunction "1_1") (pintype "passive"))
      (node (ref "U$1") (pin "15") (pinfunction "CAP_15") (pintype "bidirectional"))
    )
    (net (code "125") (name "Net-(U$3-QA)") (class "Default")
      (node (ref "LCD") (pin "DB0") (pinfunction "DB0_DB0") (pintype "bidirectional"))
      (node (ref "U$3") (pin "3") (pinfunction "QA_3") (pintype "bidirectional"))
    )
    (net (code "126") (name "Net-(U$3-QB)") (class "Default")
      (node (ref "LCD") (pin "DB1") (pinfunction "DB1_DB1") (pintype "bidirectional"))
      (node (ref "U$3") (pin "4") (pinfunction "QB_4") (pintype "bidirectional"))
    )
    (net (code "127") (name "Net-(U$3-QC)") (class "Default")
      (node (ref "LCD") (pin "DB2") (pinfunction "DB2_DB2") (pintype "bidirectional"))
      (node (ref "U$3") (pin "5") (pinfunction "QC_5") (pintype "bidirectional"))
    )
    (net (code "128") (name "Net-(U$3-QD)") (class "Default")
      (node (ref "LCD") (pin "DB3") (pinfunction "DB3_DB3") (pintype "bidirectional"))
      (node (ref "U$3") (pin "6") (pinfunction "QD_6") (pintype "bidirectional"))
    )
    (net (code "129") (name "Net-(U$3-QE)") (class "Default")
      (node (ref "LCD") (pin "DB4") (pinfunction "DB4_DB4") (pintype "bidirectional"))
      (node (ref "U$3") (pin "10") (pinfunction "QE_10") (pintype "bidirectional"))
    )
    (net (code "130") (name "Net-(U$3-QF)") (class "Default")
      (node (ref "LCD") (pin "DB5") (pinfunction "DB5_DB5") (pintype "bidirectional"))
      (node (ref "U$3") (pin "11") (pinfunction "QF_11") (pintype "bidirectional"))
    )
    (net (code "131") (name "Net-(U$3-QG)") (class "Default")
      (node (ref "LCD") (pin "DB6") (pinfunction "DB6_DB6") (pintype "bidirectional"))
      (node (ref "U$3") (pin "12") (pinfunction "QG_12") (pintype "bidirectional"))
    )
    (net (code "132") (name "Net-(U$3-QH)") (class "Default")
      (node (ref "LCD") (pin "DB7") (pinfunction "DB7_DB7") (pintype "bidirectional"))
      (node (ref "U$3") (pin "13") (pinfunction "QH_13") (pintype "bidirectional"))
    )
    (net (code "133") (name "Net-(U1-CCPA)") (class "Default")
      (node (ref "C9") (pin "1") (pinfunction "1_1") (pintype "passive"))
      (node (ref "U1") (pin "P$41") (pinfunction "CCPA_P$41") (pintype "bidirectional"))
    )
    (net (code "134") (name "Net-(U1-CCPB)") (class "Default")
      (node (ref "C8") (pin "2") (pinfunction "2_2") (pintype "passive"))
      (node (ref "U1") (pin "P$19") (pinfunction "CCPB_P$19") (pintype "bidirectional"))
    )
    (net (code "135") (name "Net-(U2-BOOT)") (class "Default")
      (node (ref "C32") (pin "1") (pinfunction "1_1") (pintype "passive"))
      (node (ref "U2") (pin "11") (pinfunction "BOOT_11") (pintype "bidirectional"))
    )
    (net (code "136") (name "Net-(U2-EN{slash}SYNC)") (class "Default")
      (node (ref "R34") (pin "1") (pinfunction "1_1") (pintype "passive"))
      (node (ref "U2") (pin "3") (pinfunction "EN/SYNC_3") (pintype "bidirectional"))
    )
    (net (code "137") (name "Net-(U2-FB)") (class "Default")
      (node (ref "R32") (pin "1") (pinfunction "1_1") (pintype "passive"))
      (node (ref "R33") (pin "2") (pinfunction "2_2") (pintype "passive"))
      (node (ref "U2") (pin "1") (pinfunction "FB_1") (pintype "bidirectional"))
    )
    (net (code "138") (name "Net-(U2-VCC)") (class "Default")
      (node (ref "C33") (pin "2") (pinfunction "2_2") (pintype "passive"))
      (node (ref "U2") (pin "12") (pinfunction "VCC_12") (pintype "bidirectional"))
    )
    (net (code "139") (name "Net-(U6-IO1_1)") (class "Default")
      (node (ref "U6") (pin "P$1") (pinfunction "IO1_1_P$1") (pintype "bidirectional"))
      (node (ref "USB1") (pin "D-") (pinfunction "D-_D-") (pintype "bidirectional"))
    )
    (net (code "140") (name "Net-(U6-IO1_2)") (class "Default")
      (node (ref "R49") (pin "1") (pinfunction "1_1") (pintype "passive"))
      (node (ref "U6") (pin "P$6") (pinfunction "IO1_2_P$6") (pintype "bidirectional"))
    )
    (net (code "141") (name "Net-(U6-IO2_1)") (class "Default")
      (node (ref "U6") (pin "P$3") (pinfunction "IO2_1_P$3") (pintype "bidirectional"))
      (node (ref "USB1") (pin "D+") (pinfunction "D+_D+") (pintype "bidirectional"))
    )
    (net (code "142") (name "Net-(U6-IO2_2)") (class "Default")
      (node (ref "R48") (pin "1") (pinfunction "1_1") (pintype "passive"))
      (node (ref "U6") (pin "P$4") (pinfunction "IO2_2_P$4") (pintype "bidirectional"))
    )
    (net (code "143") (name "Net-(U8-IO1_1)") (class "Default")
      (node (ref "U8") (pin "P$1") (pinfunction "IO1_1_P$1") (pintype "bidirectional"))
      (node (ref "USB2") (pin "D-") (pinfunction "D-_D-") (pintype "bidirectional"))
    )
    (net (code "144") (name "Net-(U8-IO1_2)") (class "Default")
      (node (ref "R46") (pin "1") (pinfunction "1_1") (pintype "passive"))
      (node (ref "U8") (pin "P$6") (pinfunction "IO1_2_P$6") (pintype "bidirectional"))
    )
    (net (code "145") (name "Net-(U8-IO2_1)") (class "Default")
      (node (ref "U8") (pin "P$3") (pinfunction "IO2_1_P$3") (pintype "bidirectional"))
      (node (ref "USB2") (pin "D+") (pinfunction "D+_D+") (pintype "bidirectional"))
    )
    (net (code "146") (name "Net-(U8-IO2_2)") (class "Default")
      (node (ref "R47") (pin "1") (pinfunction "1_1") (pintype "passive"))
      (node (ref "U8") (pin "P$4") (pinfunction "IO2_2_P$4") (pintype "bidirectional"))
    )
    (net (code "147") (name "Net-(XB1-PWM0{slash}RSSI)") (class "Default")
      (node (ref "LED5") (pin "A") (pinfunction "A_A") (pintype "passive"))
      (node (ref "XB1") (pin "6") (pinfunction "PWM0/RSSI_6") (pintype "output"))
    )
    (net (code "148") (name "unconnected-(J6-Pad1)") (class "Default")
      (node (ref "J6") (pin "1") (pinfunction "1_1") (pintype "passive"))
    )
    (net (code "149") (name "unconnected-(J6-Pad6)") (class "Default")
      (node (ref "J6") (pin "6") (pinfunction "6_6") (pintype "passive"))
    )
    (net (code "150") (name "unconnected-(SD-NC-Pad1)") (class "Default")
      (node (ref "SD") (pin "1") (pinfunction "NC_1") (pintype "bidirectional"))
    )
    (net (code "151") (name "unconnected-(SD-RSV-Pad8)") (class "Default")
      (node (ref "SD") (pin "8") (pinfunction "RSV_8") (pintype "bidirectional"))
    )
    (net (code "152") (name "unconnected-(U2-PGOOD-Pad2)") (class "Default")
      (node (ref "U2") (pin "2") (pinfunction "PGOOD_2") (pintype "bidirectional"))
    )
    (net (code "153") (name "unconnected-(U3-NC-Pad1)") (class "Default")
      (node (ref "U3") (pin "1") (pinfunction "NC_1") (pintype "bidirectional"))
    )
    (net (code "154") (name "unconnected-(USB2-PadID)") (class "Default")
      (node (ref "USB2") (pin "ID") (pinfunction "ID_ID") (pintype "bidirectional"))
    )
    (net (code "155") (name "unconnected-(XB1-AD0{slash}DIO0-Pad20)") (class "Default")
      (node (ref "XB1") (pin "20") (pinfunction "AD0/DIO0_20") (pintype "bidirectional"))
    )
    (net (code "156") (name "unconnected-(XB1-AD1{slash}DIO1-Pad19)") (class "Default")
      (node (ref "XB1") (pin "19") (pinfunction "AD1/DIO1_19") (pintype "bidirectional"))
    )
    (net (code "157") (name "unconnected-(XB1-AD2{slash}DIO2-Pad18)") (class "Default")
      (node (ref "XB1") (pin "18") (pinfunction "AD2/DIO2_18") (pintype "bidirectional"))
    )
    (net (code "158") (name "unconnected-(XB1-ASSOC{slash}AD5{slash}DIO5-Pad15)") (class "Default")
      (node (ref "XB1") (pin "15") (pinfunction "ASSOC/AD5/DIO5_15") (pintype "bidirectional"))
    )
    (net (code "159") (name "unconnected-(XB1-CD{slash}DOUT_EN{slash}DO8-Pad4)") (class "Default")
      (node (ref "XB1") (pin "4") (pinfunction "CD/DOUT_EN/DO8_4") (pintype "output"))
    )
    (net (code "160") (name "unconnected-(XB1-COORD_SEL{slash}AD3{slash}DIO3-Pad17)") (class "Default")
      (node (ref "XB1") (pin "17") (pinfunction "COORD_SEL/AD3/DIO3_17") (pintype "bidirectional"))
    )
    (net (code "161") (name "unconnected-(XB1-ON{slash}~{SLEEP}-Pad13)") (class "Default")
      (node (ref "XB1") (pin "13") (pinfunction "ON/~{SLEEP}_13") (pintype "output"))
    )
    (net (code "162") (name "unconnected-(XB1-RF_TX{slash}AD4{slash}DIO4-Pad11)") (class "Default")
      (node (ref "XB1") (pin "11") (pinfunction "RF_TX/AD4/DIO4_11") (pintype "bidirectional"))
    )
    (net (code "163") (name "unconnected-(XB1-VREF-Pad14)") (class "Default")
      (node (ref "XB1") (pin "14") (pinfunction "VREF_14") (pintype "input"))
    )
    (net (code "164") (name "unconnected-(XB1-~{CTS}{slash}DIO7-Pad12)") (class "Default")
      (node (ref "XB1") (pin "12") (pinfunction "~{CTS}/DIO7_12") (pintype "bidirectional"))
    )
    (net (code "165") (name "unconnected-(XB1-~{DTR}{slash}SLEEP_RQ{slash}DI8-Pad9)") (class "Default")
      (node (ref "XB1") (pin "9") (pinfunction "~{DTR}/SLEEP_RQ/DI8_9") (pintype "bidirectional"))
    )
    (net (code "166") (name "unconnected-(XB1-~{RESET}-Pad5)") (class "Default")
      (node (ref "XB1") (pin "5") (pinfunction "~{RESET}_5") (pintype "input"))
    )
    (net (code "167") (name "unconnected-(XB1-~{RTS}{slash}AD6{slash}DIO6-Pad16)") (class "Default")
      (node (ref "XB1") (pin "16") (pinfunction "~{RTS}/AD6/DIO6_16") (pintype "bidirectional"))
    )
  )
)
